# breakout.net
KiCad netlist of a schematic drawn in EAGLE
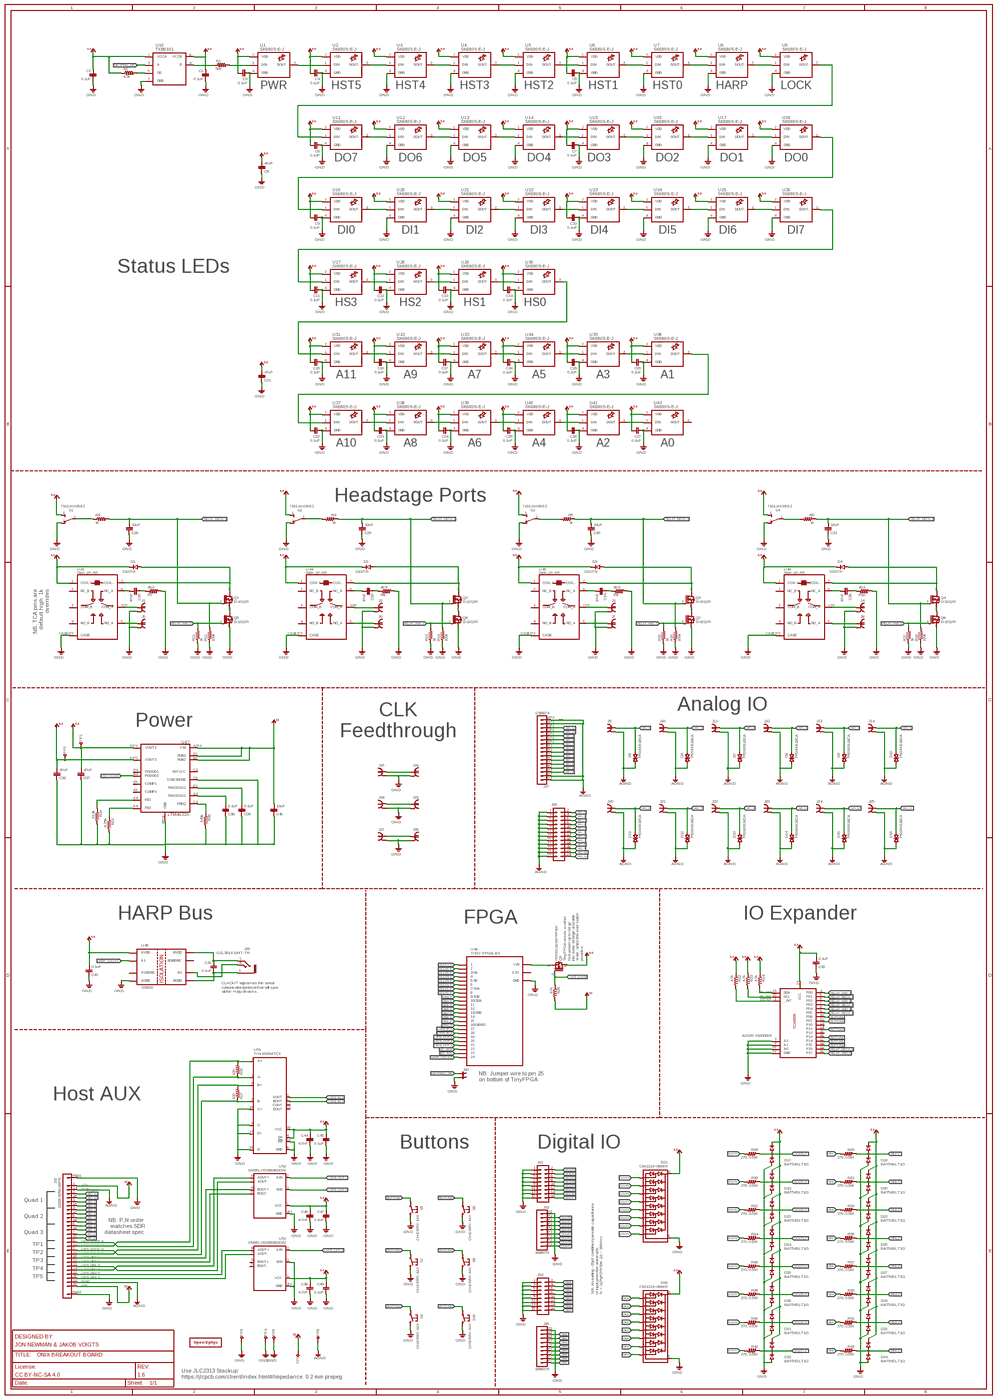
[diagram p0: schematic, sheet 1, overview]
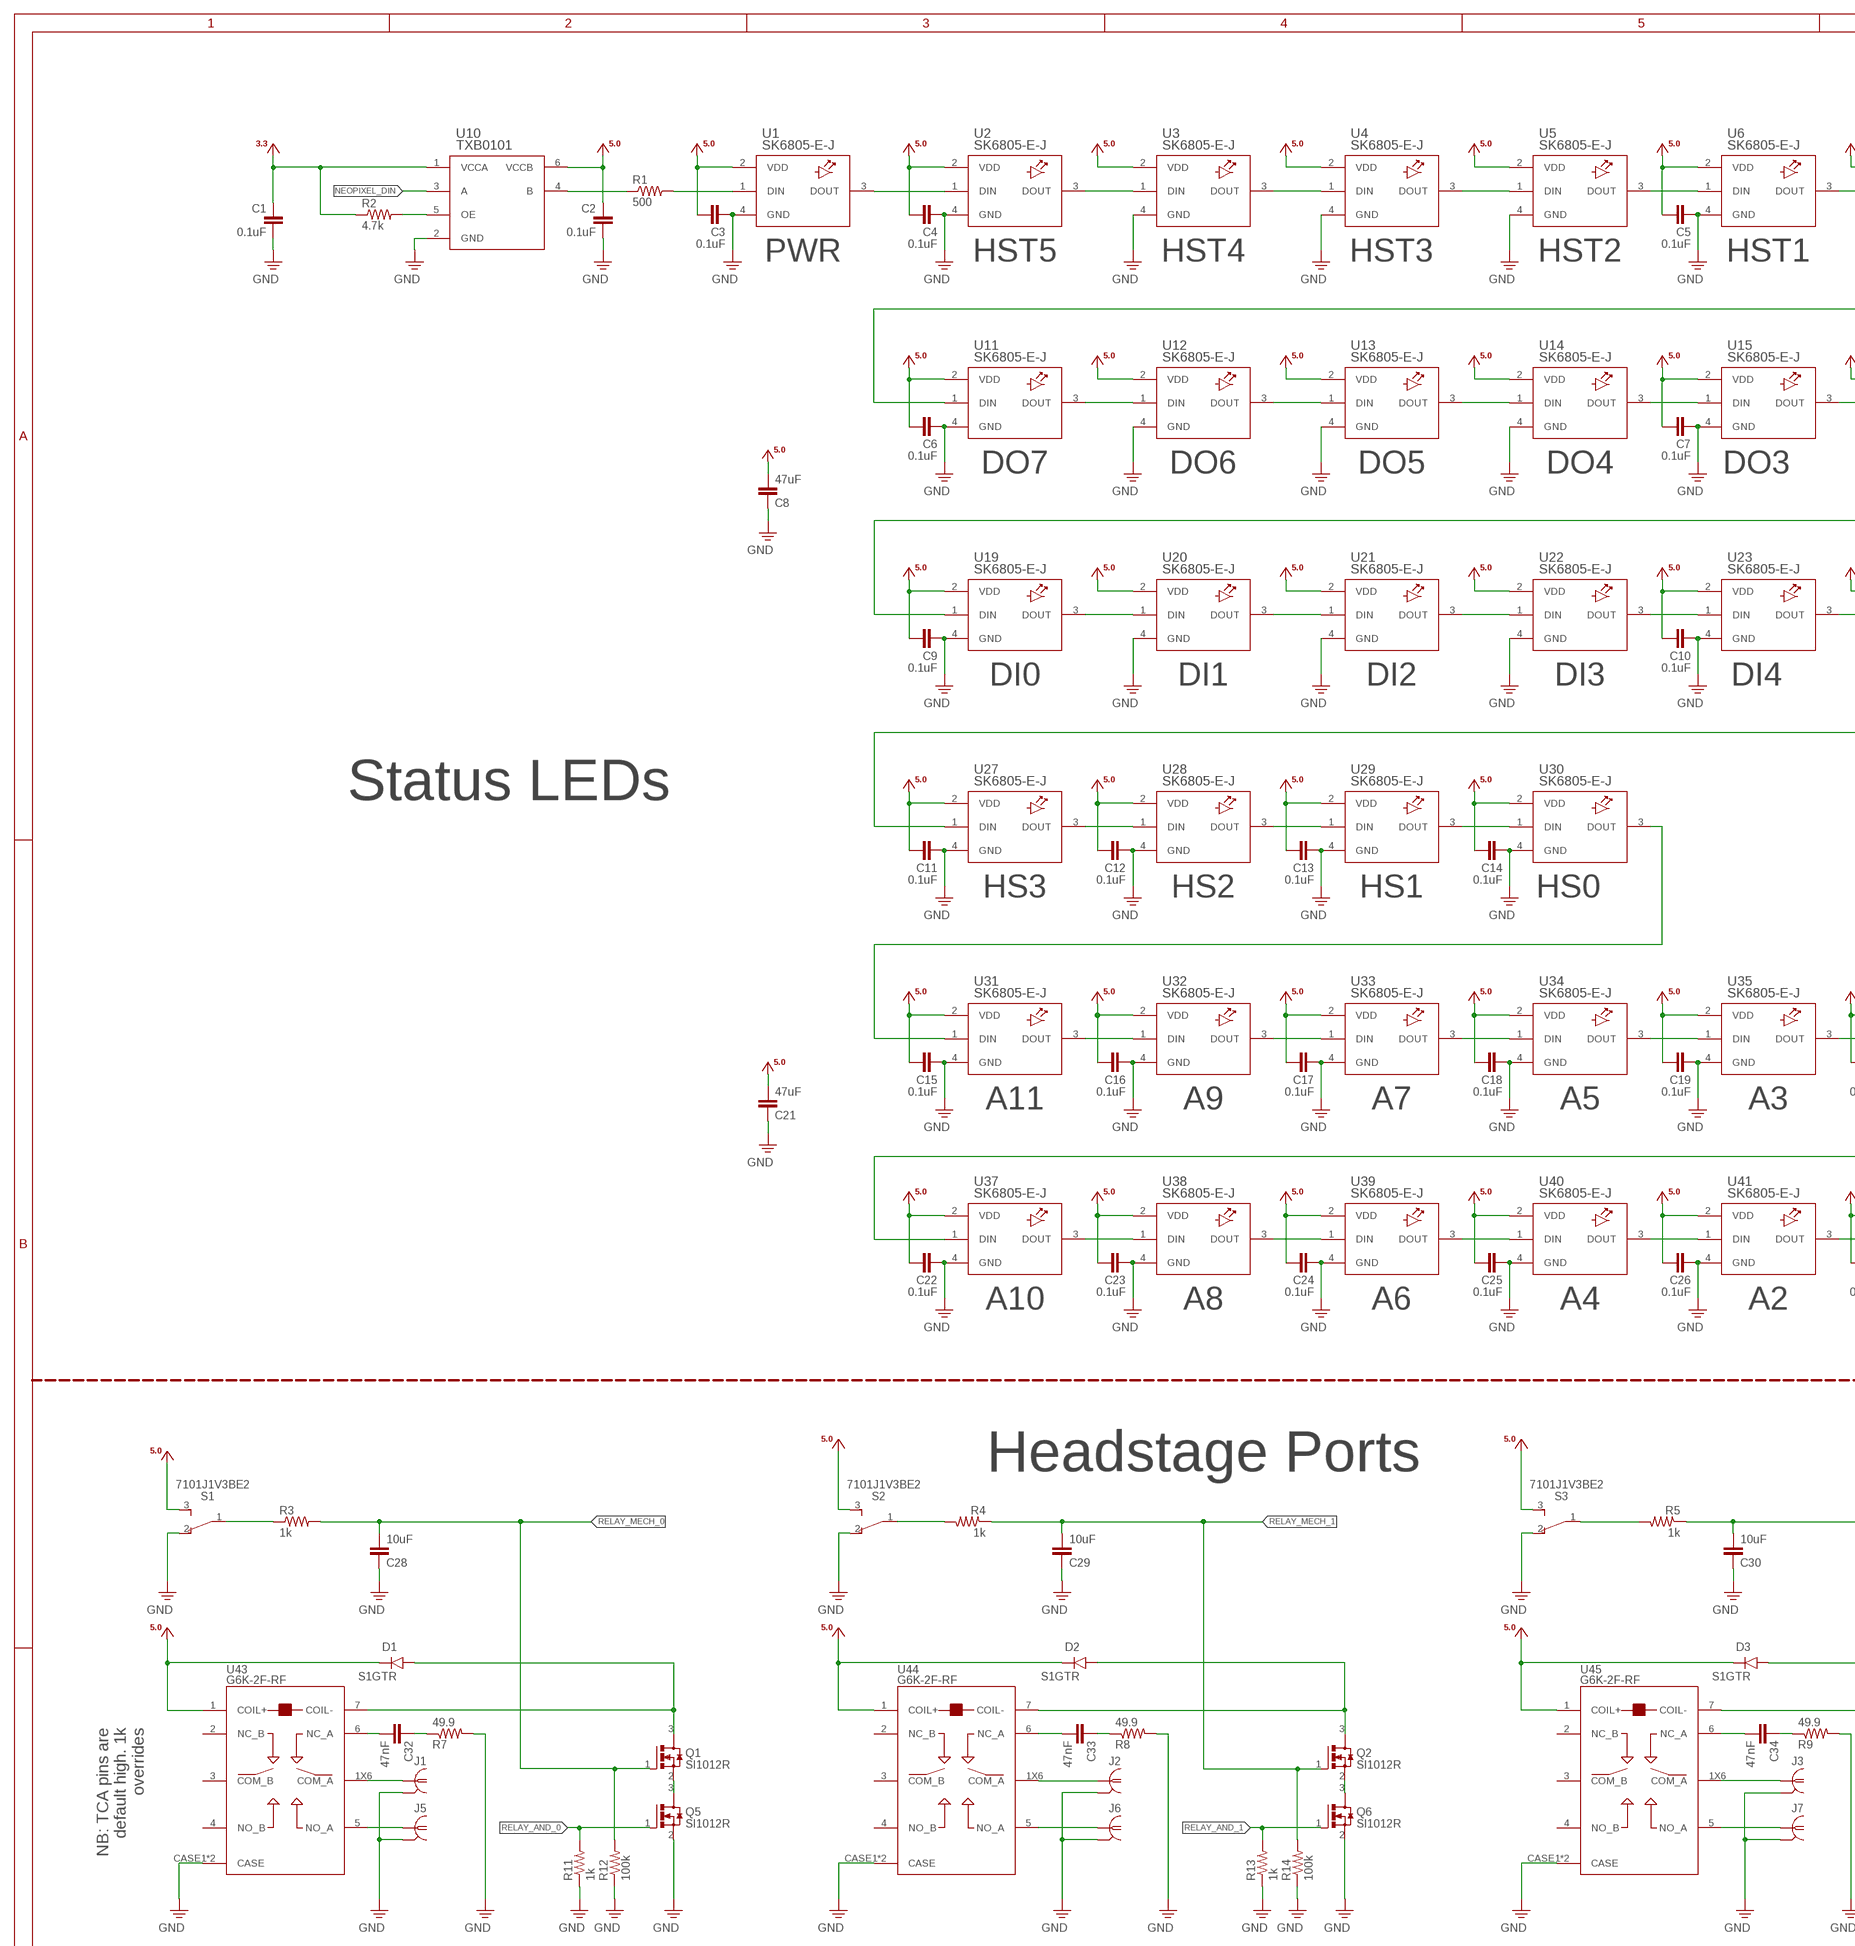
[diagram p1: schematic, sheet 1, part 1 of 4]
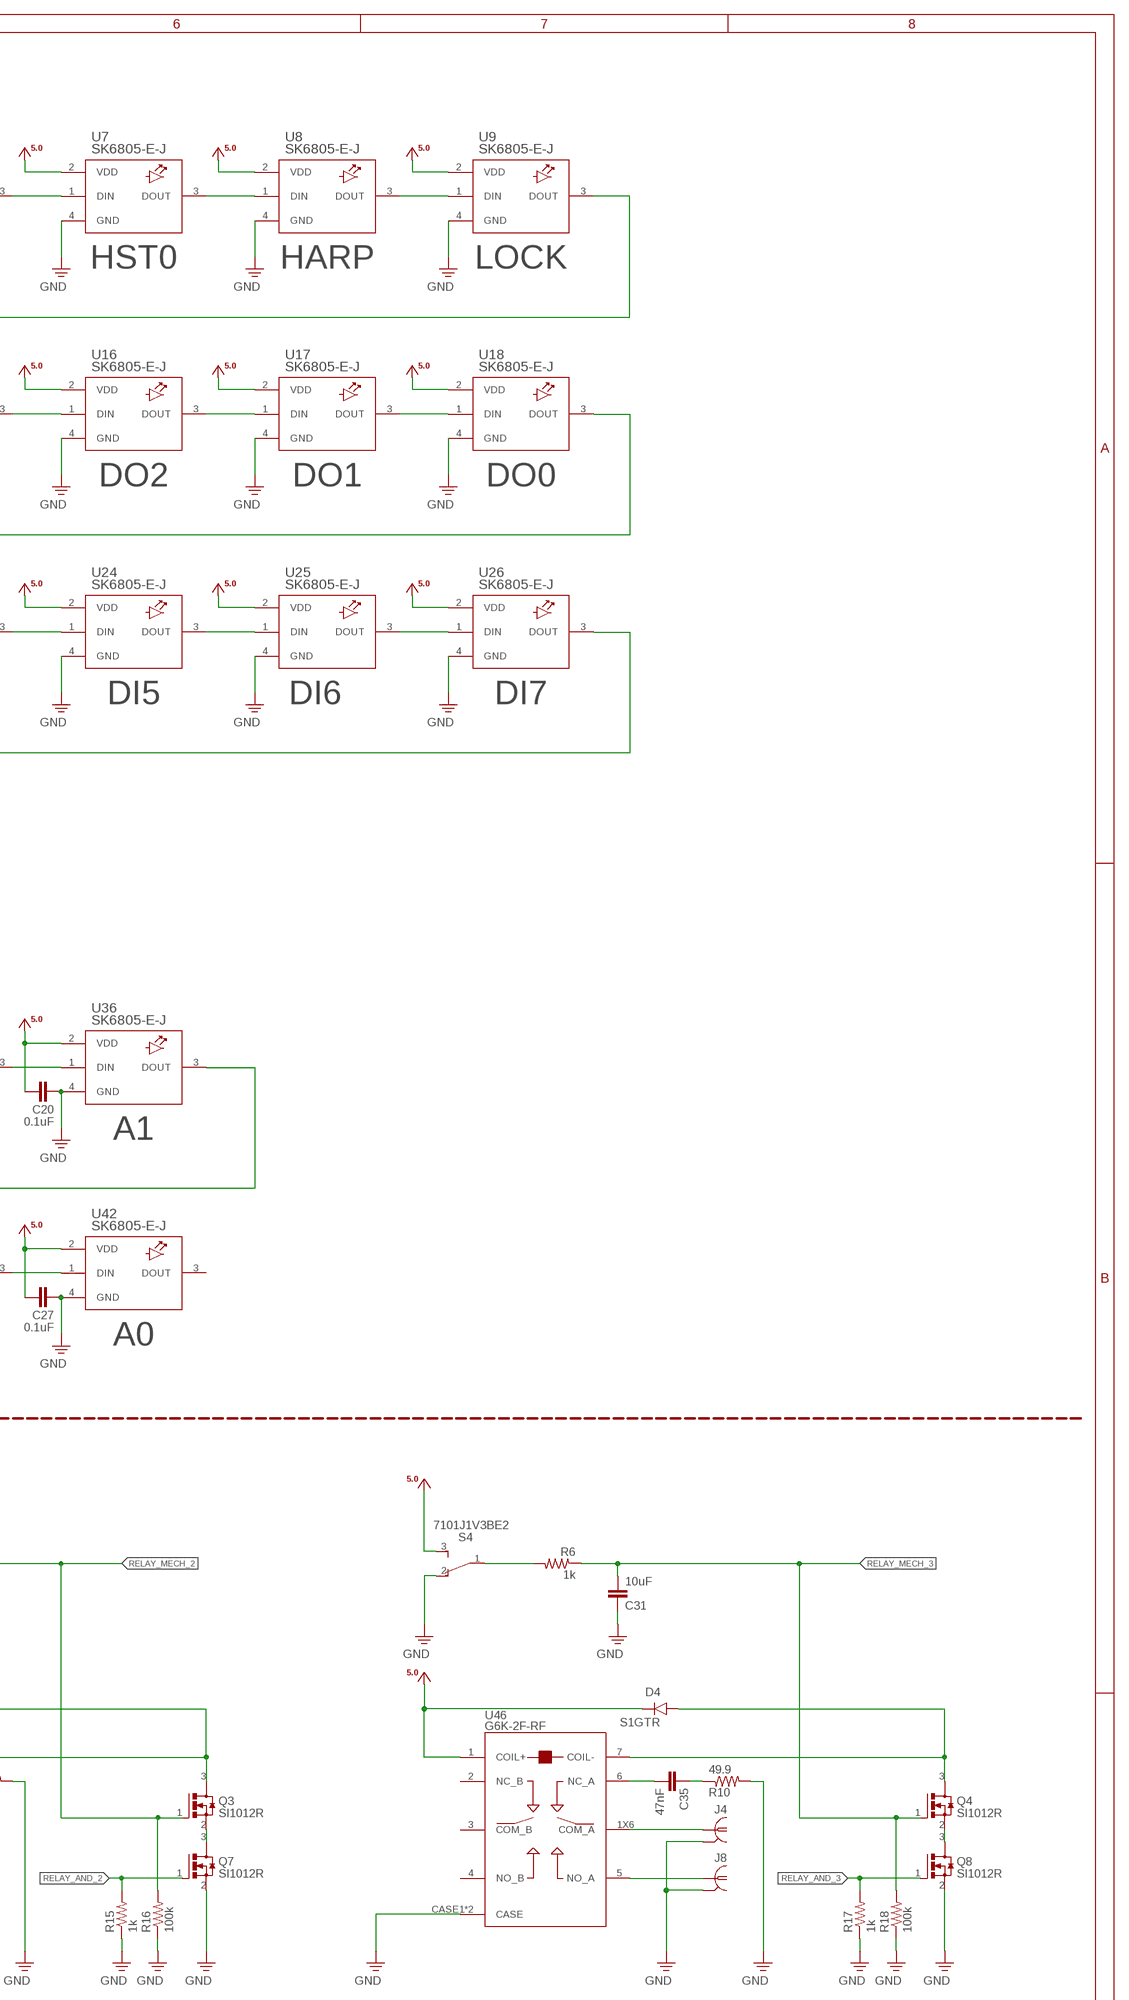
[diagram p2: schematic, sheet 1, part 2 of 4]
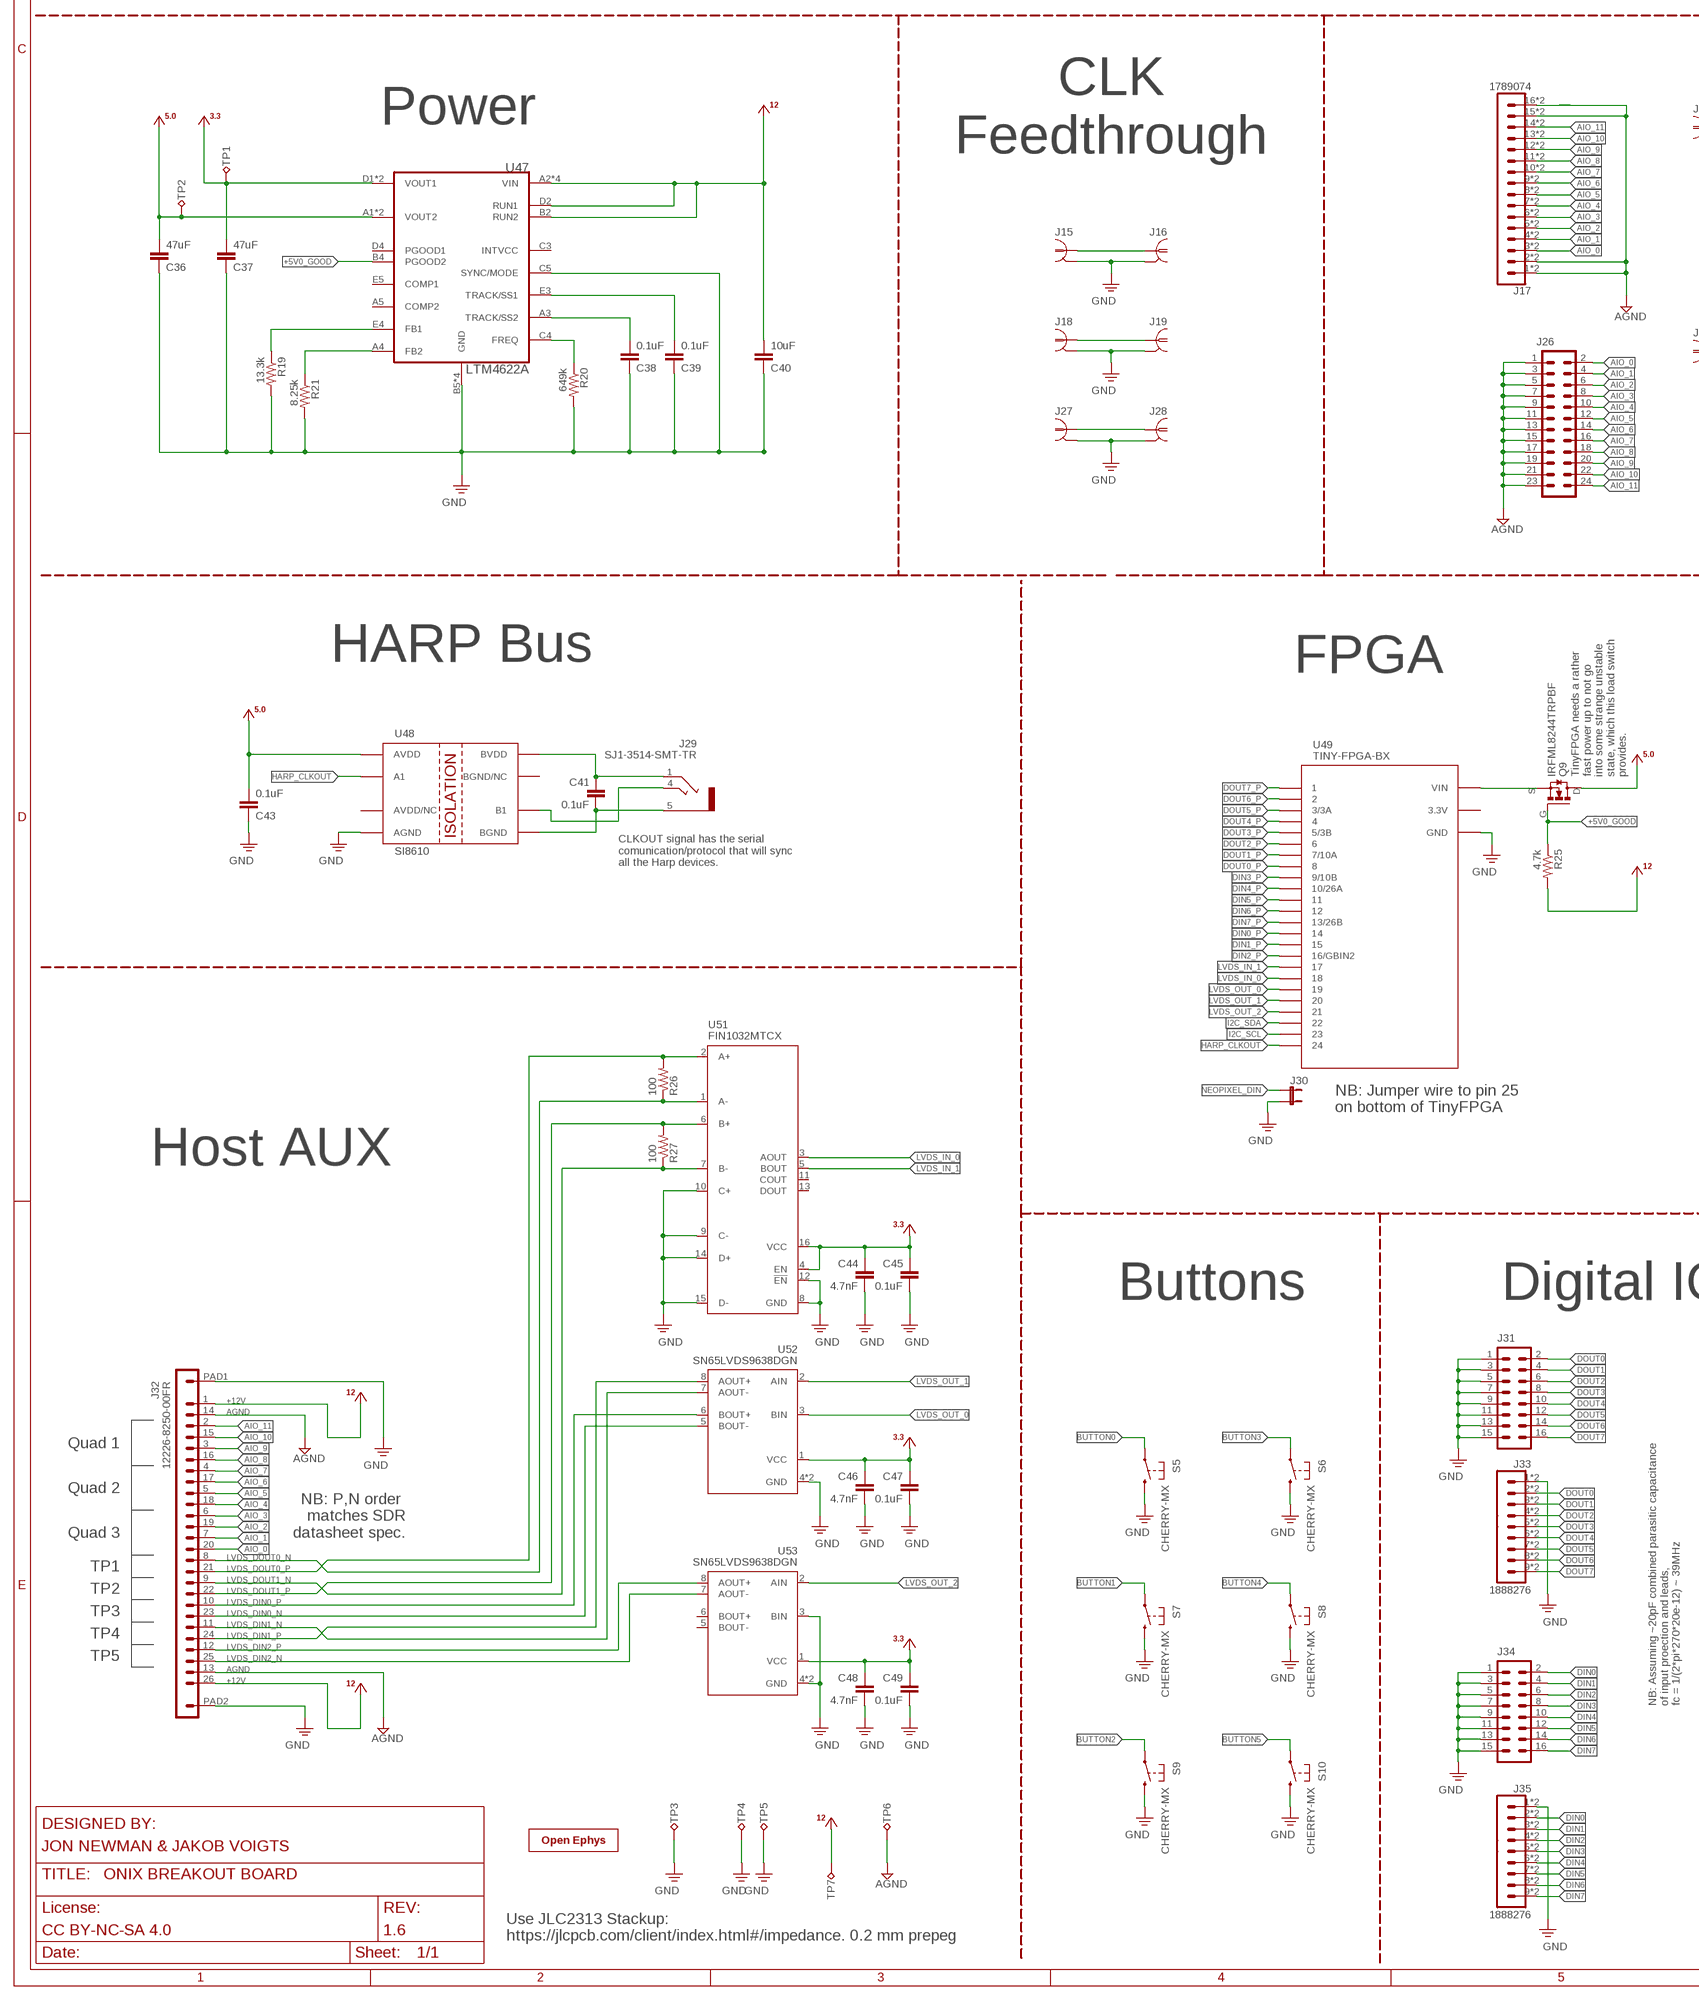
[diagram p3: schematic, sheet 1, part 3 of 4]
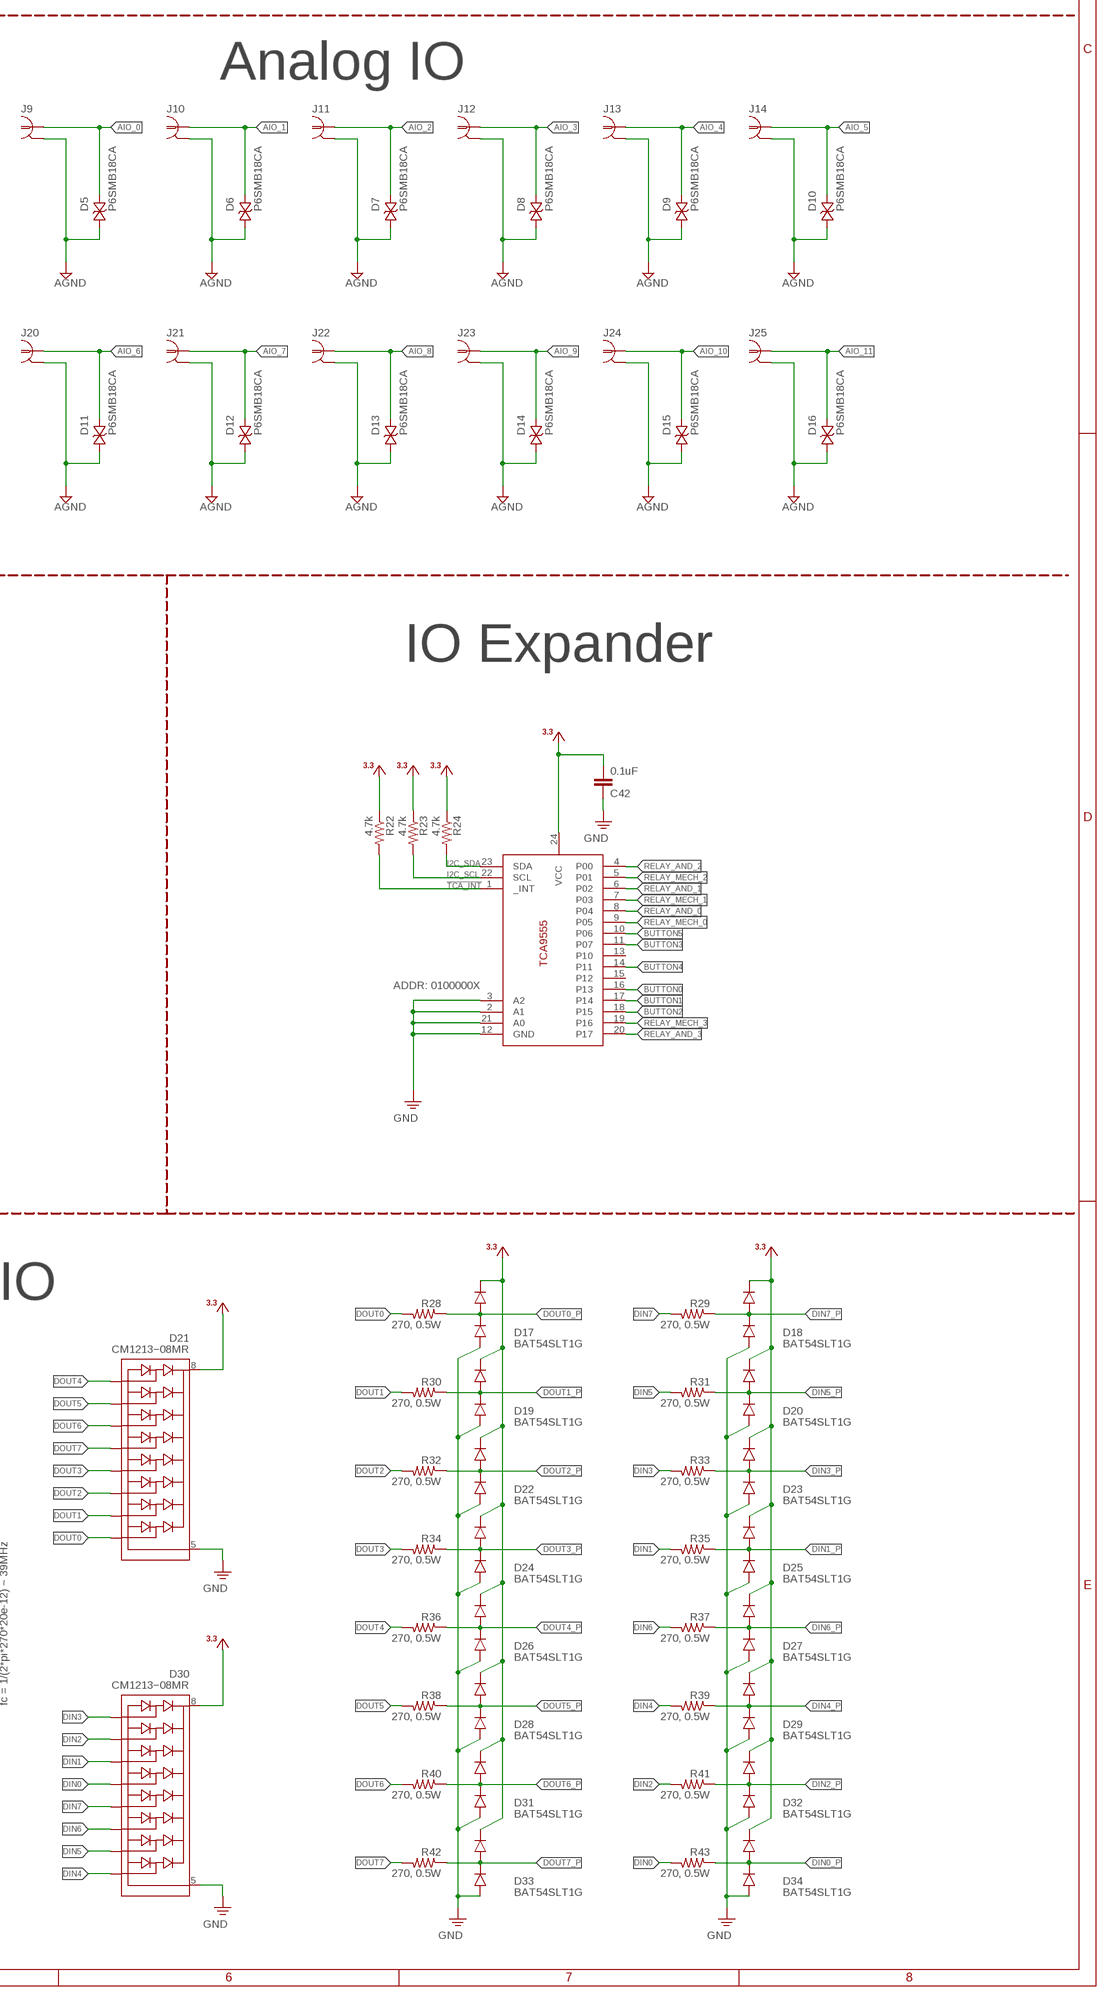
[diagram p4: schematic, sheet 1, part 4 of 4]

(export (version "E")
  (design (tool "Eeschema 10.0.6"))
  (components
    (comp (ref "C1")
      (value "0.1uF")
      (footprint "eagle-import:0402")
      (libsource (lib "eagle-import") (part "C_0402"))
    )
    (comp (ref "C2")
      (value "0.1uF")
      (footprint "eagle-import:0402")
      (libsource (lib "eagle-import") (part "C_0402"))
    )
    (comp (ref "C3")
      (value "0.1uF")
      (footprint "eagle-import:0402")
      (libsource (lib "eagle-import") (part "C_0402"))
    )
    (comp (ref "C4")
      (value "0.1uF")
      (footprint "eagle-import:0402")
      (libsource (lib "eagle-import") (part "C_0402"))
    )
    (comp (ref "C5")
      (value "0.1uF")
      (footprint "eagle-import:0402")
      (libsource (lib "eagle-import") (part "C_0402"))
    )
    (comp (ref "C6")
      (value "0.1uF")
      (footprint "eagle-import:0402")
      (libsource (lib "eagle-import") (part "C_0402"))
    )
    (comp (ref "C7")
      (value "0.1uF")
      (footprint "eagle-import:0402")
      (libsource (lib "eagle-import") (part "C_0402"))
    )
    (comp (ref "C8")
      (value "47uF")
      (footprint "eagle-import:1210")
      (libsource (lib "eagle-import") (part "C_1210"))
    )
    (comp (ref "C9")
      (value "0.1uF")
      (footprint "eagle-import:0402")
      (libsource (lib "eagle-import") (part "C_0402"))
    )
    (comp (ref "C10")
      (value "0.1uF")
      (footprint "eagle-import:0402")
      (libsource (lib "eagle-import") (part "C_0402"))
    )
    (comp (ref "C11")
      (value "0.1uF")
      (footprint "eagle-import:0402")
      (libsource (lib "eagle-import") (part "C_0402"))
    )
    (comp (ref "C12")
      (value "0.1uF")
      (footprint "eagle-import:0402")
      (libsource (lib "eagle-import") (part "C_0402"))
    )
    (comp (ref "C13")
      (value "0.1uF")
      (footprint "eagle-import:0402")
      (libsource (lib "eagle-import") (part "C_0402"))
    )
    (comp (ref "C14")
      (value "0.1uF")
      (footprint "eagle-import:0402")
      (libsource (lib "eagle-import") (part "C_0402"))
    )
    (comp (ref "C15")
      (value "0.1uF")
      (footprint "eagle-import:0402")
      (libsource (lib "eagle-import") (part "C_0402"))
    )
    (comp (ref "C16")
      (value "0.1uF")
      (footprint "eagle-import:0402")
      (libsource (lib "eagle-import") (part "C_0402"))
    )
    (comp (ref "C17")
      (value "0.1uF")
      (footprint "eagle-import:0402")
      (libsource (lib "eagle-import") (part "C_0402"))
    )
    (comp (ref "C18")
      (value "0.1uF")
      (footprint "eagle-import:0402")
      (libsource (lib "eagle-import") (part "C_0402"))
    )
    (comp (ref "C19")
      (value "0.1uF")
      (footprint "eagle-import:0402")
      (libsource (lib "eagle-import") (part "C_0402"))
    )
    (comp (ref "C20")
      (value "0.1uF")
      (footprint "eagle-import:0402")
      (libsource (lib "eagle-import") (part "C_0402"))
    )
    (comp (ref "C21")
      (value "47uF")
      (footprint "eagle-import:1210")
      (libsource (lib "eagle-import") (part "C_1210"))
    )
    (comp (ref "C22")
      (value "0.1uF")
      (footprint "eagle-import:0402")
      (libsource (lib "eagle-import") (part "C_0402"))
    )
    (comp (ref "C23")
      (value "0.1uF")
      (footprint "eagle-import:0402")
      (libsource (lib "eagle-import") (part "C_0402"))
    )
    (comp (ref "C24")
      (value "0.1uF")
      (footprint "eagle-import:0402")
      (libsource (lib "eagle-import") (part "C_0402"))
    )
    (comp (ref "C25")
      (value "0.1uF")
      (footprint "eagle-import:0402")
      (libsource (lib "eagle-import") (part "C_0402"))
    )
    (comp (ref "C26")
      (value "0.1uF")
      (footprint "eagle-import:0402")
      (libsource (lib "eagle-import") (part "C_0402"))
    )
    (comp (ref "C27")
      (value "0.1uF")
      (footprint "eagle-import:0402")
      (libsource (lib "eagle-import") (part "C_0402"))
    )
    (comp (ref "C28")
      (value "10uF")
      (footprint "eagle-import:0805")
      (fields (field (name "PARTNO") "C2012X5R1Cxxxxxxx"))
      (libsource (lib "eagle-import") (part "C_0805"))
    )
    (comp (ref "C29")
      (value "10uF")
      (footprint "eagle-import:0805")
      (fields (field (name "PARTNO") "C2012X5R1Cxxxxxxx"))
      (libsource (lib "eagle-import") (part "C_0805"))
    )
    (comp (ref "C30")
      (value "10uF")
      (footprint "eagle-import:0805")
      (fields (field (name "PARTNO") "C2012X5R1Cxxxxxxx"))
      (libsource (lib "eagle-import") (part "C_0805"))
    )
    (comp (ref "C31")
      (value "10uF")
      (footprint "eagle-import:0805")
      (fields (field (name "PARTNO") "C2012X5R1Cxxxxxxx"))
      (libsource (lib "eagle-import") (part "C_0805"))
    )
    (comp (ref "C32")
      (value "47nF")
      (footprint "eagle-import:0402")
      (libsource (lib "eagle-import") (part "C_0402"))
    )
    (comp (ref "C33")
      (value "47nF")
      (footprint "eagle-import:0402")
      (libsource (lib "eagle-import") (part "C_0402"))
    )
    (comp (ref "C34")
      (value "47nF")
      (footprint "eagle-import:0402")
      (libsource (lib "eagle-import") (part "C_0402"))
    )
    (comp (ref "C35")
      (value "47nF")
      (footprint "eagle-import:0402")
      (libsource (lib "eagle-import") (part "C_0402"))
    )
    (comp (ref "C36")
      (value "47uF")
      (footprint "eagle-import:1210")
      (libsource (lib "eagle-import") (part "C_1210"))
    )
    (comp (ref "C37")
      (value "47uF")
      (footprint "eagle-import:1210")
      (libsource (lib "eagle-import") (part "C_1210"))
    )
    (comp (ref "C38")
      (value "0.1uF")
      (footprint "eagle-import:0402")
      (libsource (lib "eagle-import") (part "C_0402"))
    )
    (comp (ref "C39")
      (value "0.1uF")
      (footprint "eagle-import:0402")
      (libsource (lib "eagle-import") (part "C_0402"))
    )
    (comp (ref "C40")
      (value "10uF")
      (footprint "eagle-import:0805")
      (fields (field (name "PARTNO") "C2012X5R1Cxxxxxxx"))
      (libsource (lib "eagle-import") (part "C_0805"))
    )
    (comp (ref "C41")
      (value "0.1uF")
      (footprint "eagle-import:0402")
      (libsource (lib "eagle-import") (part "C_0402"))
    )
    (comp (ref "C42")
      (value "0.1uF")
      (footprint "eagle-import:0402")
      (libsource (lib "eagle-import") (part "C_0402"))
    )
    (comp (ref "C43")
      (value "0.1uF")
      (footprint "eagle-import:0402")
      (libsource (lib "eagle-import") (part "C_0402"))
    )
    (comp (ref "C44")
      (value "4.7nF")
      (footprint "eagle-import:0402")
      (libsource (lib "eagle-import") (part "C_0402"))
    )
    (comp (ref "C45")
      (value "0.1uF")
      (footprint "eagle-import:0402")
      (libsource (lib "eagle-import") (part "C_0402"))
    )
    (comp (ref "C46")
      (value "4.7nF")
      (footprint "eagle-import:0402")
      (libsource (lib "eagle-import") (part "C_0402"))
    )
    (comp (ref "C47")
      (value "0.1uF")
      (footprint "eagle-import:0402")
      (libsource (lib "eagle-import") (part "C_0402"))
    )
    (comp (ref "C48")
      (value "4.7nF")
      (footprint "eagle-import:0402")
      (libsource (lib "eagle-import") (part "C_0402"))
    )
    (comp (ref "C49")
      (value "0.1uF")
      (footprint "eagle-import:0402")
      (libsource (lib "eagle-import") (part "C_0402"))
    )
    (comp (ref "D1")
      (value "S1GTR")
      (footprint "eagle-import:SMA-DO214AC")
      (libsource (lib "eagle-import") (part "DIODE_S1B-13-F"))
    )
    (comp (ref "D2")
      (value "S1GTR")
      (footprint "eagle-import:SMA-DO214AC")
      (libsource (lib "eagle-import") (part "DIODE_S1B-13-F"))
    )
    (comp (ref "D3")
      (value "S1GTR")
      (footprint "eagle-import:SMA-DO214AC")
      (libsource (lib "eagle-import") (part "DIODE_S1B-13-F"))
    )
    (comp (ref "D4")
      (value "S1GTR")
      (footprint "eagle-import:SMA-DO214AC")
      (libsource (lib "eagle-import") (part "DIODE_S1B-13-F"))
    )
    (comp (ref "D5")
      (value "P6SMB18CA")
      (footprint "eagle-import:SMA-DO214AC")
      (libsource (lib "eagle-import") (part "TVS-DIODE-BI_DO214"))
    )
    (comp (ref "D6")
      (value "P6SMB18CA")
      (footprint "eagle-import:SMA-DO214AC")
      (libsource (lib "eagle-import") (part "TVS-DIODE-BI_DO214"))
    )
    (comp (ref "D7")
      (value "P6SMB18CA")
      (footprint "eagle-import:SMA-DO214AC")
      (libsource (lib "eagle-import") (part "TVS-DIODE-BI_DO214"))
    )
    (comp (ref "D8")
      (value "P6SMB18CA")
      (footprint "eagle-import:SMA-DO214AC")
      (libsource (lib "eagle-import") (part "TVS-DIODE-BI_DO214"))
    )
    (comp (ref "D9")
      (value "P6SMB18CA")
      (footprint "eagle-import:SMA-DO214AC")
      (libsource (lib "eagle-import") (part "TVS-DIODE-BI_DO214"))
    )
    (comp (ref "D10")
      (value "P6SMB18CA")
      (footprint "eagle-import:SMA-DO214AC")
      (libsource (lib "eagle-import") (part "TVS-DIODE-BI_DO214"))
    )
    (comp (ref "D11")
      (value "P6SMB18CA")
      (footprint "eagle-import:SMA-DO214AC")
      (libsource (lib "eagle-import") (part "TVS-DIODE-BI_DO214"))
    )
    (comp (ref "D12")
      (value "P6SMB18CA")
      (footprint "eagle-import:SMA-DO214AC")
      (libsource (lib "eagle-import") (part "TVS-DIODE-BI_DO214"))
    )
    (comp (ref "D13")
      (value "P6SMB18CA")
      (footprint "eagle-import:SMA-DO214AC")
      (libsource (lib "eagle-import") (part "TVS-DIODE-BI_DO214"))
    )
    (comp (ref "D14")
      (value "P6SMB18CA")
      (footprint "eagle-import:SMA-DO214AC")
      (libsource (lib "eagle-import") (part "TVS-DIODE-BI_DO214"))
    )
    (comp (ref "D15")
      (value "P6SMB18CA")
      (footprint "eagle-import:SMA-DO214AC")
      (libsource (lib "eagle-import") (part "TVS-DIODE-BI_DO214"))
    )
    (comp (ref "D16")
      (value "P6SMB18CA")
      (footprint "eagle-import:SMA-DO214AC")
      (libsource (lib "eagle-import") (part "TVS-DIODE-BI_DO214"))
    )
    (comp (ref "D17")
      (value "BAT54SLT1G")
      (footprint "eagle-import:SOT23")
      (libsource (lib "eagle-import") (part "DIODE2_SOT23"))
    )
    (comp (ref "D18")
      (value "BAT54SLT1G")
      (footprint "eagle-import:SOT23")
      (libsource (lib "eagle-import") (part "DIODE2_SOT23"))
    )
    (comp (ref "D19")
      (value "BAT54SLT1G")
      (footprint "eagle-import:SOT23")
      (libsource (lib "eagle-import") (part "DIODE2_SOT23"))
    )
    (comp (ref "D20")
      (value "BAT54SLT1G")
      (footprint "eagle-import:SOT23")
      (libsource (lib "eagle-import") (part "DIODE2_SOT23"))
    )
    (comp (ref "D21")
      (value "CM1213−08MR")
      (footprint "eagle-import:MSOP-10-3X3")
      (libsource (lib "eagle-import") (part "TVS-DIODE-BI-8_MSOP"))
    )
    (comp (ref "D22")
      (value "BAT54SLT1G")
      (footprint "eagle-import:SOT23")
      (libsource (lib "eagle-import") (part "DIODE2_SOT23"))
    )
    (comp (ref "D23")
      (value "BAT54SLT1G")
      (footprint "eagle-import:SOT23")
      (libsource (lib "eagle-import") (part "DIODE2_SOT23"))
    )
    (comp (ref "D24")
      (value "BAT54SLT1G")
      (footprint "eagle-import:SOT23")
      (libsource (lib "eagle-import") (part "DIODE2_SOT23"))
    )
    (comp (ref "D25")
      (value "BAT54SLT1G")
      (footprint "eagle-import:SOT23")
      (libsource (lib "eagle-import") (part "DIODE2_SOT23"))
    )
    (comp (ref "D26")
      (value "BAT54SLT1G")
      (footprint "eagle-import:SOT23")
      (libsource (lib "eagle-import") (part "DIODE2_SOT23"))
    )
    (comp (ref "D27")
      (value "BAT54SLT1G")
      (footprint "eagle-import:SOT23")
      (libsource (lib "eagle-import") (part "DIODE2_SOT23"))
    )
    (comp (ref "D28")
      (value "BAT54SLT1G")
      (footprint "eagle-import:SOT23")
      (libsource (lib "eagle-import") (part "DIODE2_SOT23"))
    )
    (comp (ref "D29")
      (value "BAT54SLT1G")
      (footprint "eagle-import:SOT23")
      (libsource (lib "eagle-import") (part "DIODE2_SOT23"))
    )
    (comp (ref "D30")
      (value "CM1213−08MR")
      (footprint "eagle-import:MSOP-10-3X3")
      (libsource (lib "eagle-import") (part "TVS-DIODE-BI-8_MSOP"))
    )
    (comp (ref "D31")
      (value "BAT54SLT1G")
      (footprint "eagle-import:SOT23")
      (libsource (lib "eagle-import") (part "DIODE2_SOT23"))
    )
    (comp (ref "D32")
      (value "BAT54SLT1G")
      (footprint "eagle-import:SOT23")
      (libsource (lib "eagle-import") (part "DIODE2_SOT23"))
    )
    (comp (ref "D33")
      (value "BAT54SLT1G")
      (footprint "eagle-import:SOT23")
      (libsource (lib "eagle-import") (part "DIODE2_SOT23"))
    )
    (comp (ref "D34")
      (value "BAT54SLT1G")
      (footprint "eagle-import:SOT23")
      (libsource (lib "eagle-import") (part "DIODE2_SOT23"))
    )
    (comp (ref "J1")
      (value "COAX_SMA-VERT")
      (footprint "eagle-import:SMA_JACK_142-0701-201")
      (libsource (lib "eagle-import") (part "COAX_SMA-VERT"))
    )
    (comp (ref "J2")
      (value "COAX_SMA-VERT")
      (footprint "eagle-import:SMA_JACK_142-0701-201")
      (libsource (lib "eagle-import") (part "COAX_SMA-VERT"))
    )
    (comp (ref "J3")
      (value "COAX_SMA-VERT")
      (footprint "eagle-import:SMA_JACK_142-0701-201")
      (libsource (lib "eagle-import") (part "COAX_SMA-VERT"))
    )
    (comp (ref "J4")
      (value "COAX_SMA-VERT")
      (footprint "eagle-import:SMA_JACK_142-0701-201")
      (libsource (lib "eagle-import") (part "COAX_SMA-VERT"))
    )
    (comp (ref "J5")
      (value "COAX_MMCX-THRU")
      (footprint "eagle-import:MMCX-THRU")
      (libsource (lib "eagle-import") (part "COAX_MMCX-THRU"))
    )
    (comp (ref "J6")
      (value "COAX_MMCX-THRU")
      (footprint "eagle-import:MMCX-THRU")
      (libsource (lib "eagle-import") (part "COAX_MMCX-THRU"))
    )
    (comp (ref "J7")
      (value "COAX_MMCX-THRU")
      (footprint "eagle-import:MMCX-THRU")
      (libsource (lib "eagle-import") (part "COAX_MMCX-THRU"))
    )
    (comp (ref "J8")
      (value "COAX_MMCX-THRU")
      (footprint "eagle-import:MMCX-THRU")
      (libsource (lib "eagle-import") (part "COAX_MMCX-THRU"))
    )
    (comp (ref "J9")
      (value "COAX_0731010360")
      (footprint "eagle-import:0731010360")
      (libsource (lib "eagle-import") (part "COAX_0731010360"))
    )
    (comp (ref "J10")
      (value "COAX_0731010360")
      (footprint "eagle-import:0731010360")
      (libsource (lib "eagle-import") (part "COAX_0731010360"))
    )
    (comp (ref "J11")
      (value "COAX_0731010360")
      (footprint "eagle-import:0731010360")
      (libsource (lib "eagle-import") (part "COAX_0731010360"))
    )
    (comp (ref "J12")
      (value "COAX_0731010360")
      (footprint "eagle-import:0731010360")
      (libsource (lib "eagle-import") (part "COAX_0731010360"))
    )
    (comp (ref "J13")
      (value "COAX_0731010360")
      (footprint "eagle-import:0731010360")
      (libsource (lib "eagle-import") (part "COAX_0731010360"))
    )
    (comp (ref "J14")
      (value "COAX_0731010360")
      (footprint "eagle-import:0731010360")
      (libsource (lib "eagle-import") (part "COAX_0731010360"))
    )
    (comp (ref "J15")
      (value "COAX_MMCX-THRU")
      (footprint "eagle-import:MMCX-THRU")
      (libsource (lib "eagle-import") (part "COAX_MMCX-THRU"))
    )
    (comp (ref "J16")
      (value "COAX_SMA-VERT")
      (footprint "eagle-import:SMA_JACK_142-0701-201")
      (libsource (lib "eagle-import") (part "COAX_SMA-VERT"))
    )
    (comp (ref "J17")
      (value "1789074")
      (footprint "eagle-import:SCREW16-2")
      (libsource (lib "eagle-import") (part "PINHD-1X16"))
    )
    (comp (ref "J18")
      (value "COAX_MMCX-THRU")
      (footprint "eagle-import:MMCX-THRU")
      (libsource (lib "eagle-import") (part "COAX_MMCX-THRU"))
    )
    (comp (ref "J19")
      (value "COAX_SMA-VERT")
      (footprint "eagle-import:SMA_JACK_142-0701-201")
      (libsource (lib "eagle-import") (part "COAX_SMA-VERT"))
    )
    (comp (ref "J20")
      (value "COAX_0731010360")
      (footprint "eagle-import:0731010360")
      (libsource (lib "eagle-import") (part "COAX_0731010360"))
    )
    (comp (ref "J21")
      (value "COAX_0731010360")
      (footprint "eagle-import:0731010360")
      (libsource (lib "eagle-import") (part "COAX_0731010360"))
    )
    (comp (ref "J22")
      (value "COAX_0731010360")
      (footprint "eagle-import:0731010360")
      (libsource (lib "eagle-import") (part "COAX_0731010360"))
    )
    (comp (ref "J23")
      (value "COAX_0731010360")
      (footprint "eagle-import:0731010360")
      (libsource (lib "eagle-import") (part "COAX_0731010360"))
    )
    (comp (ref "J24")
      (value "COAX_0731010360")
      (footprint "eagle-import:0731010360")
      (libsource (lib "eagle-import") (part "COAX_0731010360"))
    )
    (comp (ref "J25")
      (value "COAX_0731010360")
      (footprint "eagle-import:0731010360")
      (libsource (lib "eagle-import") (part "COAX_0731010360"))
    )
    (comp (ref "J26")
      (value "69168-124HLF")
      (footprint "eagle-import:2X12-BIG")
      (libsource (lib "eagle-import") (part "PINHD-2X12_0.1{dblquote}"))
    )
    (comp (ref "J27")
      (value "COAX_MMCX-THRU")
      (footprint "eagle-import:MMCX-THRU")
      (libsource (lib "eagle-import") (part "COAX_MMCX-THRU"))
    )
    (comp (ref "J28")
      (value "COAX_SMA-VERT")
      (footprint "eagle-import:SMA_JACK_142-0701-201")
      (libsource (lib "eagle-import") (part "COAX_SMA-VERT"))
    )
    (comp (ref "J29")
      (value "SJ1-3514-SMT-TR")
      (footprint "eagle-import:35RASMT2BHNTRX")
      (libsource (lib "eagle-import") (part "STEREO_JACK"))
    )
    (comp (ref "J30")
      (value "JP2E_THRU-HOLE")
      (footprint "eagle-import:JP2")
      (libsource (lib "eagle-import") (part "JP2E_THRU-HOLE"))
    )
    (comp (ref "J31")
      (value "69168-116HLF")
      (footprint "eagle-import:2X08-BIG")
      (libsource (lib "eagle-import") (part "PINHD-2X8_THRU"))
    )
    (comp (ref "J32")
      (value "12226-8250-00FR")
      (footprint "eagle-import:12226-82X0-00XX")
      (libsource (lib "eagle-import") (part "PINHD-1X26_122"))
    )
    (comp (ref "J33")
      (value "1888276")
      (footprint "eagle-import:SCREW9-2")
      (libsource (lib "eagle-import") (part "PINHD-1X9_SCREW2"))
    )
    (comp (ref "J34")
      (value "69168-116HLF")
      (footprint "eagle-import:2X08-BIG")
      (libsource (lib "eagle-import") (part "PINHD-2X8_THRU"))
    )
    (comp (ref "J35")
      (value "1888276")
      (footprint "eagle-import:SCREW9-2")
      (libsource (lib "eagle-import") (part "PINHD-1X9_SCREW2"))
    )
    (comp (ref "Q1")
      (value "SI1012R")
      (footprint "eagle-import:SC75")
      (libsource (lib "eagle-import") (part "N-MOSFET_SC75-GSD"))
    )
    (comp (ref "Q2")
      (value "SI1012R")
      (footprint "eagle-import:SC75")
      (libsource (lib "eagle-import") (part "N-MOSFET_SC75-GSD"))
    )
    (comp (ref "Q3")
      (value "SI1012R")
      (footprint "eagle-import:SC75")
      (libsource (lib "eagle-import") (part "N-MOSFET_SC75-GSD"))
    )
    (comp (ref "Q4")
      (value "SI1012R")
      (footprint "eagle-import:SC75")
      (libsource (lib "eagle-import") (part "N-MOSFET_SC75-GSD"))
    )
    (comp (ref "Q5")
      (value "SI1012R")
      (footprint "eagle-import:SC75")
      (libsource (lib "eagle-import") (part "N-MOSFET_SC75-GSD"))
    )
    (comp (ref "Q6")
      (value "SI1012R")
      (footprint "eagle-import:SC75")
      (libsource (lib "eagle-import") (part "N-MOSFET_SC75-GSD"))
    )
    (comp (ref "Q7")
      (value "SI1012R")
      (footprint "eagle-import:SC75")
      (libsource (lib "eagle-import") (part "N-MOSFET_SC75-GSD"))
    )
    (comp (ref "Q8")
      (value "SI1012R")
      (footprint "eagle-import:SC75")
      (libsource (lib "eagle-import") (part "N-MOSFET_SC75-GSD"))
    )
    (comp (ref "Q9")
      (value "IRFML8244TRPBF")
      (footprint "eagle-import:SOT23-GSD")
      (libsource (lib "eagle-import") (part "N-MOSFET_SOT23-GSD"))
    )
    (comp (ref "R1")
      (value "500")
      (footprint "eagle-import:0402")
      (libsource (lib "eagle-import") (part "R_0402"))
    )
    (comp (ref "R2")
      (value "4.7k")
      (footprint "eagle-import:0402")
      (libsource (lib "eagle-import") (part "R_0402"))
    )
    (comp (ref "R3")
      (value "1k")
      (footprint "eagle-import:0402")
      (libsource (lib "eagle-import") (part "R_0402"))
    )
    (comp (ref "R4")
      (value "1k")
      (footprint "eagle-import:0402")
      (libsource (lib "eagle-import") (part "R_0402"))
    )
    (comp (ref "R5")
      (value "1k")
      (footprint "eagle-import:0402")
      (libsource (lib "eagle-import") (part "R_0402"))
    )
    (comp (ref "R6")
      (value "1k")
      (footprint "eagle-import:0402")
      (libsource (lib "eagle-import") (part "R_0402"))
    )
    (comp (ref "R7")
      (value "49.9")
      (footprint "eagle-import:0402")
      (libsource (lib "eagle-import") (part "R_0402"))
    )
    (comp (ref "R8")
      (value "49.9")
      (footprint "eagle-import:0402")
      (libsource (lib "eagle-import") (part "R_0402"))
    )
    (comp (ref "R9")
      (value "49.9")
      (footprint "eagle-import:0402")
      (libsource (lib "eagle-import") (part "R_0402"))
    )
    (comp (ref "R10")
      (value "49.9")
      (footprint "eagle-import:0402")
      (libsource (lib "eagle-import") (part "R_0402"))
    )
    (comp (ref "R11")
      (value "1k")
      (footprint "eagle-import:0402")
      (libsource (lib "eagle-import") (part "R_0402"))
    )
    (comp (ref "R12")
      (value "100k")
      (footprint "eagle-import:0402")
      (libsource (lib "eagle-import") (part "R_0402"))
    )
    (comp (ref "R13")
      (value "1k")
      (footprint "eagle-import:0402")
      (libsource (lib "eagle-import") (part "R_0402"))
    )
    (comp (ref "R14")
      (value "100k")
      (footprint "eagle-import:0402")
      (libsource (lib "eagle-import") (part "R_0402"))
    )
    (comp (ref "R15")
      (value "1k")
      (footprint "eagle-import:0402")
      (libsource (lib "eagle-import") (part "R_0402"))
    )
    (comp (ref "R16")
      (value "100k")
      (footprint "eagle-import:0402")
      (libsource (lib "eagle-import") (part "R_0402"))
    )
    (comp (ref "R17")
      (value "1k")
      (footprint "eagle-import:0402")
      (libsource (lib "eagle-import") (part "R_0402"))
    )
    (comp (ref "R18")
      (value "100k")
      (footprint "eagle-import:0402")
      (libsource (lib "eagle-import") (part "R_0402"))
    )
    (comp (ref "R19")
      (value "13.3k")
      (footprint "eagle-import:0402")
      (libsource (lib "eagle-import") (part "R_0402"))
    )
    (comp (ref "R20")
      (value "649k")
      (footprint "eagle-import:0402")
      (libsource (lib "eagle-import") (part "R_0402"))
    )
    (comp (ref "R21")
      (value "8.25k")
      (footprint "eagle-import:0402")
      (libsource (lib "eagle-import") (part "R_0402"))
    )
    (comp (ref "R22")
      (value "4.7k")
      (footprint "eagle-import:0402")
      (libsource (lib "eagle-import") (part "R_0402"))
    )
    (comp (ref "R23")
      (value "4.7k")
      (footprint "eagle-import:0402")
      (libsource (lib "eagle-import") (part "R_0402"))
    )
    (comp (ref "R24")
      (value "4.7k")
      (footprint "eagle-import:0402")
      (libsource (lib "eagle-import") (part "R_0402"))
    )
    (comp (ref "R25")
      (value "4.7k")
      (footprint "eagle-import:0402")
      (libsource (lib "eagle-import") (part "R_0402"))
    )
    (comp (ref "R26")
      (value "100")
      (footprint "eagle-import:0402")
      (libsource (lib "eagle-import") (part "R_0402"))
    )
    (comp (ref "R27")
      (value "100")
      (footprint "eagle-import:0402")
      (libsource (lib "eagle-import") (part "R_0402"))
    )
    (comp (ref "R28")
      (value "270, 0.5W")
      (footprint "eagle-import:0805")
      (libsource (lib "eagle-import") (part "R_0805"))
    )
    (comp (ref "R29")
      (value "270, 0.5W")
      (footprint "eagle-import:0805")
      (libsource (lib "eagle-import") (part "R_0805"))
    )
    (comp (ref "R30")
      (value "270, 0.5W")
      (footprint "eagle-import:0805")
      (libsource (lib "eagle-import") (part "R_0805"))
    )
    (comp (ref "R31")
      (value "270, 0.5W")
      (footprint "eagle-import:0805")
      (libsource (lib "eagle-import") (part "R_0805"))
    )
    (comp (ref "R32")
      (value "270, 0.5W")
      (footprint "eagle-import:0805")
      (libsource (lib "eagle-import") (part "R_0805"))
    )
    (comp (ref "R33")
      (value "270, 0.5W")
      (footprint "eagle-import:0805")
      (libsource (lib "eagle-import") (part "R_0805"))
    )
    (comp (ref "R34")
      (value "270, 0.5W")
      (footprint "eagle-import:0805")
      (libsource (lib "eagle-import") (part "R_0805"))
    )
    (comp (ref "R35")
      (value "270, 0.5W")
      (footprint "eagle-import:0805")
      (libsource (lib "eagle-import") (part "R_0805"))
    )
    (comp (ref "R36")
      (value "270, 0.5W")
      (footprint "eagle-import:0805")
      (libsource (lib "eagle-import") (part "R_0805"))
    )
    (comp (ref "R37")
      (value "270, 0.5W")
      (footprint "eagle-import:0805")
      (libsource (lib "eagle-import") (part "R_0805"))
    )
    (comp (ref "R38")
      (value "270, 0.5W")
      (footprint "eagle-import:0805")
      (libsource (lib "eagle-import") (part "R_0805"))
    )
    (comp (ref "R39")
      (value "270, 0.5W")
      (footprint "eagle-import:0805")
      (libsource (lib "eagle-import") (part "R_0805"))
    )
    (comp (ref "R40")
      (value "270, 0.5W")
      (footprint "eagle-import:0805")
      (libsource (lib "eagle-import") (part "R_0805"))
    )
    (comp (ref "R41")
      (value "270, 0.5W")
      (footprint "eagle-import:0805")
      (libsource (lib "eagle-import") (part "R_0805"))
    )
    (comp (ref "R42")
      (value "270, 0.5W")
      (footprint "eagle-import:0805")
      (libsource (lib "eagle-import") (part "R_0805"))
    )
    (comp (ref "R43")
      (value "270, 0.5W")
      (footprint "eagle-import:0805")
      (libsource (lib "eagle-import") (part "R_0805"))
    )
    (comp (ref "S1")
      (value "7101J1V3BE2")
      (footprint "eagle-import:CK_7101J1V3QE2")
      (libsource (lib "eagle-import") (part "SPDT_CK-710"))
    )
    (comp (ref "S2")
      (value "7101J1V3BE2")
      (footprint "eagle-import:CK_7101J1V3QE2")
      (libsource (lib "eagle-import") (part "SPDT_CK-710"))
    )
    (comp (ref "S3")
      (value "7101J1V3BE2")
      (footprint "eagle-import:CK_7101J1V3QE2")
      (libsource (lib "eagle-import") (part "SPDT_CK-710"))
    )
    (comp (ref "S4")
      (value "7101J1V3BE2")
      (footprint "eagle-import:CK_7101J1V3QE2")
      (libsource (lib "eagle-import") (part "SPDT_CK-710"))
    )
    (comp (ref "S5")
      (value "CHERRY-MX")
      (footprint "eagle-import:CHERRY-MX")
      (libsource (lib "eagle-import") (part "SPST_TACT2_CHERRY-MX"))
    )
    (comp (ref "S6")
      (value "CHERRY-MX")
      (footprint "eagle-import:CHERRY-MX")
      (libsource (lib "eagle-import") (part "SPST_TACT2_CHERRY-MX"))
    )
    (comp (ref "S7")
      (value "CHERRY-MX")
      (footprint "eagle-import:CHERRY-MX")
      (libsource (lib "eagle-import") (part "SPST_TACT2_CHERRY-MX"))
    )
    (comp (ref "S8")
      (value "CHERRY-MX")
      (footprint "eagle-import:CHERRY-MX")
      (libsource (lib "eagle-import") (part "SPST_TACT2_CHERRY-MX"))
    )
    (comp (ref "S9")
      (value "CHERRY-MX")
      (footprint "eagle-import:CHERRY-MX")
      (libsource (lib "eagle-import") (part "SPST_TACT2_CHERRY-MX"))
    )
    (comp (ref "S10")
      (value "CHERRY-MX")
      (footprint "eagle-import:CHERRY-MX")
      (libsource (lib "eagle-import") (part "SPST_TACT2_CHERRY-MX"))
    )
    (comp (ref "TP1")
      (value "TPTP19R")
      (footprint "eagle-import:TP19R")
      (libsource (lib "eagle-import") (part "TPTP19R"))
    )
    (comp (ref "TP2")
      (value "TPTP19R")
      (footprint "eagle-import:TP19R")
      (libsource (lib "eagle-import") (part "TPTP19R"))
    )
    (comp (ref "TP3")
      (value "TP_2MM")
      (footprint "eagle-import:TESTPOINT_2MM")
      (libsource (lib "eagle-import") (part "TP_2MM"))
    )
    (comp (ref "TP4")
      (value "TP_2MM")
      (footprint "eagle-import:TESTPOINT_2MM")
      (libsource (lib "eagle-import") (part "TP_2MM"))
    )
    (comp (ref "TP5")
      (value "TP_2MM")
      (footprint "eagle-import:TESTPOINT_2MM")
      (libsource (lib "eagle-import") (part "TP_2MM"))
    )
    (comp (ref "TP6")
      (value "TP_2MM")
      (footprint "eagle-import:TESTPOINT_2MM")
      (libsource (lib "eagle-import") (part "TP_2MM"))
    )
    (comp (ref "TP7")
      (value "TP_2MM")
      (footprint "eagle-import:TESTPOINT_2MM")
      (libsource (lib "eagle-import") (part "TP_2MM"))
    )
    (comp (ref "U1")
      (value "SK6805-E-J")
      (footprint "eagle-import:NEOPIXEL-1.5X1.5")
      (libsource (lib "eagle-import") (part "NEOPIXEL_1.5X1.5"))
    )
    (comp (ref "U2")
      (value "SK6805-E-J")
      (footprint "eagle-import:NEOPIXEL-1.5X1.5")
      (libsource (lib "eagle-import") (part "NEOPIXEL_1.5X1.5"))
    )
    (comp (ref "U3")
      (value "SK6805-E-J")
      (footprint "eagle-import:NEOPIXEL-1.5X1.5")
      (libsource (lib "eagle-import") (part "NEOPIXEL_1.5X1.5"))
    )
    (comp (ref "U4")
      (value "SK6805-E-J")
      (footprint "eagle-import:NEOPIXEL-1.5X1.5")
      (libsource (lib "eagle-import") (part "NEOPIXEL_1.5X1.5"))
    )
    (comp (ref "U5")
      (value "SK6805-E-J")
      (footprint "eagle-import:NEOPIXEL-1.5X1.5")
      (libsource (lib "eagle-import") (part "NEOPIXEL_1.5X1.5"))
    )
    (comp (ref "U6")
      (value "SK6805-E-J")
      (footprint "eagle-import:NEOPIXEL-1.5X1.5")
      (libsource (lib "eagle-import") (part "NEOPIXEL_1.5X1.5"))
    )
    (comp (ref "U7")
      (value "SK6805-E-J")
      (footprint "eagle-import:NEOPIXEL-1.5X1.5")
      (libsource (lib "eagle-import") (part "NEOPIXEL_1.5X1.5"))
    )
    (comp (ref "U8")
      (value "SK6805-E-J")
      (footprint "eagle-import:NEOPIXEL-1.5X1.5")
      (libsource (lib "eagle-import") (part "NEOPIXEL_1.5X1.5"))
    )
    (comp (ref "U9")
      (value "SK6805-E-J")
      (footprint "eagle-import:NEOPIXEL-1.5X1.5")
      (libsource (lib "eagle-import") (part "NEOPIXEL_1.5X1.5"))
    )
    (comp (ref "U10")
      (value "TXB0101")
      (footprint "eagle-import:SOT23-6")
      (libsource (lib "eagle-import") (part "LEVEL_SHIFTER_SOT23"))
    )
    (comp (ref "U11")
      (value "SK6805-E-J")
      (footprint "eagle-import:NEOPIXEL-1.5X1.5")
      (libsource (lib "eagle-import") (part "NEOPIXEL_1.5X1.5"))
    )
    (comp (ref "U12")
      (value "SK6805-E-J")
      (footprint "eagle-import:NEOPIXEL-1.5X1.5")
      (libsource (lib "eagle-import") (part "NEOPIXEL_1.5X1.5"))
    )
    (comp (ref "U13")
      (value "SK6805-E-J")
      (footprint "eagle-import:NEOPIXEL-1.5X1.5")
      (libsource (lib "eagle-import") (part "NEOPIXEL_1.5X1.5"))
    )
    (comp (ref "U14")
      (value "SK6805-E-J")
      (footprint "eagle-import:NEOPIXEL-1.5X1.5")
      (libsource (lib "eagle-import") (part "NEOPIXEL_1.5X1.5"))
    )
    (comp (ref "U15")
      (value "SK6805-E-J")
      (footprint "eagle-import:NEOPIXEL-1.5X1.5")
      (libsource (lib "eagle-import") (part "NEOPIXEL_1.5X1.5"))
    )
    (comp (ref "U16")
      (value "SK6805-E-J")
      (footprint "eagle-import:NEOPIXEL-1.5X1.5")
      (libsource (lib "eagle-import") (part "NEOPIXEL_1.5X1.5"))
    )
    (comp (ref "U17")
      (value "SK6805-E-J")
      (footprint "eagle-import:NEOPIXEL-1.5X1.5")
      (libsource (lib "eagle-import") (part "NEOPIXEL_1.5X1.5"))
    )
    (comp (ref "U18")
      (value "SK6805-E-J")
      (footprint "eagle-import:NEOPIXEL-1.5X1.5")
      (libsource (lib "eagle-import") (part "NEOPIXEL_1.5X1.5"))
    )
    (comp (ref "U19")
      (value "SK6805-E-J")
      (footprint "eagle-import:NEOPIXEL-1.5X1.5")
      (libsource (lib "eagle-import") (part "NEOPIXEL_1.5X1.5"))
    )
    (comp (ref "U20")
      (value "SK6805-E-J")
      (footprint "eagle-import:NEOPIXEL-1.5X1.5")
      (libsource (lib "eagle-import") (part "NEOPIXEL_1.5X1.5"))
    )
    (comp (ref "U21")
      (value "SK6805-E-J")
      (footprint "eagle-import:NEOPIXEL-1.5X1.5")
      (libsource (lib "eagle-import") (part "NEOPIXEL_1.5X1.5"))
    )
    (comp (ref "U22")
      (value "SK6805-E-J")
      (footprint "eagle-import:NEOPIXEL-1.5X1.5")
      (libsource (lib "eagle-import") (part "NEOPIXEL_1.5X1.5"))
    )
    (comp (ref "U23")
      (value "SK6805-E-J")
      (footprint "eagle-import:NEOPIXEL-1.5X1.5")
      (libsource (lib "eagle-import") (part "NEOPIXEL_1.5X1.5"))
    )
    (comp (ref "U24")
      (value "SK6805-E-J")
      (footprint "eagle-import:NEOPIXEL-1.5X1.5")
      (libsource (lib "eagle-import") (part "NEOPIXEL_1.5X1.5"))
    )
    (comp (ref "U25")
      (value "SK6805-E-J")
      (footprint "eagle-import:NEOPIXEL-1.5X1.5")
      (libsource (lib "eagle-import") (part "NEOPIXEL_1.5X1.5"))
    )
    (comp (ref "U26")
      (value "SK6805-E-J")
      (footprint "eagle-import:NEOPIXEL-1.5X1.5")
      (libsource (lib "eagle-import") (part "NEOPIXEL_1.5X1.5"))
    )
    (comp (ref "U27")
      (value "SK6805-E-J")
      (footprint "eagle-import:NEOPIXEL-1.5X1.5")
      (libsource (lib "eagle-import") (part "NEOPIXEL_1.5X1.5"))
    )
    (comp (ref "U28")
      (value "SK6805-E-J")
      (footprint "eagle-import:NEOPIXEL-1.5X1.5")
      (libsource (lib "eagle-import") (part "NEOPIXEL_1.5X1.5"))
    )
    (comp (ref "U29")
      (value "SK6805-E-J")
      (footprint "eagle-import:NEOPIXEL-1.5X1.5")
      (libsource (lib "eagle-import") (part "NEOPIXEL_1.5X1.5"))
    )
    (comp (ref "U30")
      (value "SK6805-E-J")
      (footprint "eagle-import:NEOPIXEL-1.5X1.5")
      (libsource (lib "eagle-import") (part "NEOPIXEL_1.5X1.5"))
    )
    (comp (ref "U31")
      (value "SK6805-E-J")
      (footprint "eagle-import:NEOPIXEL-1.5X1.5")
      (libsource (lib "eagle-import") (part "NEOPIXEL_1.5X1.5"))
    )
    (comp (ref "U32")
      (value "SK6805-E-J")
      (footprint "eagle-import:NEOPIXEL-1.5X1.5")
      (libsource (lib "eagle-import") (part "NEOPIXEL_1.5X1.5"))
    )
    (comp (ref "U33")
      (value "SK6805-E-J")
      (footprint "eagle-import:NEOPIXEL-1.5X1.5")
      (libsource (lib "eagle-import") (part "NEOPIXEL_1.5X1.5"))
    )
    (comp (ref "U34")
      (value "SK6805-E-J")
      (footprint "eagle-import:NEOPIXEL-1.5X1.5")
      (libsource (lib "eagle-import") (part "NEOPIXEL_1.5X1.5"))
    )
    (comp (ref "U35")
      (value "SK6805-E-J")
      (footprint "eagle-import:NEOPIXEL-1.5X1.5")
      (libsource (lib "eagle-import") (part "NEOPIXEL_1.5X1.5"))
    )
    (comp (ref "U36")
      (value "SK6805-E-J")
      (footprint "eagle-import:NEOPIXEL-1.5X1.5")
      (libsource (lib "eagle-import") (part "NEOPIXEL_1.5X1.5"))
    )
    (comp (ref "U37")
      (value "SK6805-E-J")
      (footprint "eagle-import:NEOPIXEL-1.5X1.5")
      (libsource (lib "eagle-import") (part "NEOPIXEL_1.5X1.5"))
    )
    (comp (ref "U38")
      (value "SK6805-E-J")
      (footprint "eagle-import:NEOPIXEL-1.5X1.5")
      (libsource (lib "eagle-import") (part "NEOPIXEL_1.5X1.5"))
    )
    (comp (ref "U39")
      (value "SK6805-E-J")
      (footprint "eagle-import:NEOPIXEL-1.5X1.5")
      (libsource (lib "eagle-import") (part "NEOPIXEL_1.5X1.5"))
    )
    (comp (ref "U40")
      (value "SK6805-E-J")
      (footprint "eagle-import:NEOPIXEL-1.5X1.5")
      (libsource (lib "eagle-import") (part "NEOPIXEL_1.5X1.5"))
    )
    (comp (ref "U41")
      (value "SK6805-E-J")
      (footprint "eagle-import:NEOPIXEL-1.5X1.5")
      (libsource (lib "eagle-import") (part "NEOPIXEL_1.5X1.5"))
    )
    (comp (ref "U42")
      (value "SK6805-E-J")
      (footprint "eagle-import:NEOPIXEL-1.5X1.5")
      (libsource (lib "eagle-import") (part "NEOPIXEL_1.5X1.5"))
    )
    (comp (ref "U43")
      (value "G6K-2F-RF")
      (footprint "eagle-import:G6KU-2F-RF")
      (libsource (lib "eagle-import") (part "G6KU-2F-RF-TR09DC5"))
    )
    (comp (ref "U44")
      (value "G6K-2F-RF")
      (footprint "eagle-import:G6KU-2F-RF")
      (libsource (lib "eagle-import") (part "G6KU-2F-RF-TR09DC5"))
    )
    (comp (ref "U45")
      (value "G6K-2F-RF")
      (footprint "eagle-import:G6KU-2F-RF")
      (libsource (lib "eagle-import") (part "G6KU-2F-RF-TR09DC5"))
    )
    (comp (ref "U46")
      (value "G6K-2F-RF")
      (footprint "eagle-import:G6KU-2F-RF")
      (libsource (lib "eagle-import") (part "G6KU-2F-RF-TR09DC5"))
    )
    (comp (ref "U47")
      (value "LTM4622A")
      (footprint "eagle-import:BGA_5X5_625X625")
      (libsource (lib "eagle-import") (part "LTM4622_BGA"))
    )
    (comp (ref "U48")
      (value "SI8610")
      (footprint "eagle-import:SO-08")
      (libsource (lib "eagle-import") (part "SI8610"))
    )
    (comp (ref "U49")
      (value "TINY-FPGA-BX")
      (footprint "eagle-import:TINY-FPGA-BX_BASIC")
      (libsource (lib "eagle-import") (part "TINY-FPGA-BX_BASIC"))
    )
    (comp (ref "U50")
      (value "TCA9555")
      (footprint "eagle-import:TSSOP-24")
      (libsource (lib "eagle-import") (part "TCA9555"))
    )
    (comp (ref "U51")
      (value "FIN1032MTCX")
      (footprint "eagle-import:TSSOP-16")
      (libsource (lib "eagle-import") (part "LVDS_RECEIVER_QUAD_TSSOP"))
    )
    (comp (ref "U52")
      (value "SN65LVDS9638DGN")
      (footprint "eagle-import:MSOP-8-PAD-3X3")
      (libsource (lib "eagle-import") (part "LVDS_DRIVER_DUAL_MSOP"))
    )
    (comp (ref "U53")
      (value "SN65LVDS9638DGN")
      (footprint "eagle-import:MSOP-8-PAD-3X3")
      (libsource (lib "eagle-import") (part "LVDS_DRIVER_DUAL_MSOP"))
    )
    (comp (ref "X")
      (value "OE-LOGO_28X20")
      (footprint "eagle-import:OE-LOGO-28X20")
      (libsource (lib "eagle-import") (part "OE-LOGO_28X20"))
    )
  )
  (nets
    (net (code "1") (name "+3V3") (class "Default")
      (node (ref "C1") (pin "1") (pinfunction "1_1") (pintype "passive"))
      (node (ref "C37") (pin "2") (pinfunction "2_2") (pintype "passive"))
      (node (ref "C42") (pin "2") (pinfunction "2_2") (pintype "passive"))
      (node (ref "C44") (pin "1") (pinfunction "1_1") (pintype "passive"))
      (node (ref "C45") (pin "1") (pinfunction "1_1") (pintype "passive"))
      (node (ref "C46") (pin "1") (pinfunction "1_1") (pintype "passive"))
      (node (ref "C47") (pin "1") (pinfunction "1_1") (pintype "passive"))
      (node (ref "C48") (pin "1") (pinfunction "1_1") (pintype "passive"))
      (node (ref "C49") (pin "1") (pinfunction "1_1") (pintype "passive"))
      (node (ref "D17") (pin "2") (pinfunction "C_2") (pintype "passive"))
      (node (ref "D18") (pin "2") (pinfunction "C_2") (pintype "passive"))
      (node (ref "D19") (pin "2") (pinfunction "C_2") (pintype "passive"))
      (node (ref "D20") (pin "2") (pinfunction "C_2") (pintype "passive"))
      (node (ref "D21") (pin "8") (pinfunction "VCC_8") (pintype "power_in"))
      (node (ref "D22") (pin "2") (pinfunction "C_2") (pintype "passive"))
      (node (ref "D23") (pin "2") (pinfunction "C_2") (pintype "passive"))
      (node (ref "D24") (pin "2") (pinfunction "C_2") (pintype "passive"))
      (node (ref "D25") (pin "2") (pinfunction "C_2") (pintype "passive"))
      (node (ref "D26") (pin "2") (pinfunction "C_2") (pintype "passive"))
      (node (ref "D27") (pin "2") (pinfunction "C_2") (pintype "passive"))
      (node (ref "D28") (pin "2") (pinfunction "C_2") (pintype "passive"))
      (node (ref "D29") (pin "2") (pinfunction "C_2") (pintype "passive"))
      (node (ref "D30") (pin "8") (pinfunction "VCC_8") (pintype "power_in"))
      (node (ref "D31") (pin "2") (pinfunction "C_2") (pintype "passive"))
      (node (ref "D32") (pin "2") (pinfunction "C_2") (pintype "passive"))
      (node (ref "D33") (pin "2") (pinfunction "C_2") (pintype "passive"))
      (node (ref "D34") (pin "2") (pinfunction "C_2") (pintype "passive"))
      (node (ref "R2") (pin "1") (pinfunction "1_1") (pintype "passive"))
      (node (ref "R22") (pin "1") (pinfunction "1_1") (pintype "passive"))
      (node (ref "R23") (pin "1") (pinfunction "1_1") (pintype "passive"))
      (node (ref "R24") (pin "1") (pinfunction "1_1") (pintype "passive"))
      (node (ref "TP1") (pin "TP") (pinfunction "TP_TP") (pintype "bidirectional"))
      (node (ref "U10") (pin "1") (pinfunction "VCCA_1") (pintype "power_in"))
      (node (ref "U47") (pin "D1") (pinfunction "VOUT1_D1") (pintype "power_in"))
      (node (ref "U47") (pin "E1") (pinfunction "VOUT1_E1") (pintype "power_in"))
      (node (ref "U50") (pin "24") (pinfunction "VCC_24") (pintype "bidirectional"))
      (node (ref "U51") (pin "16") (pinfunction "VCC_16") (pintype "power_in"))
      (node (ref "U51") (pin "4") (pinfunction "EN_4") (pintype "input"))
      (node (ref "U52") (pin "1") (pinfunction "VCC_1") (pintype "power_in"))
      (node (ref "U53") (pin "1") (pinfunction "VCC_1") (pintype "power_in"))
    )
    (net (code "2") (name "+5V") (class "Default")
      (node (ref "C10") (pin "2") (pinfunction "2_2") (pintype "passive"))
      (node (ref "C11") (pin "2") (pinfunction "2_2") (pintype "passive"))
      (node (ref "C12") (pin "2") (pinfunction "2_2") (pintype "passive"))
      (node (ref "C13") (pin "2") (pinfunction "2_2") (pintype "passive"))
      (node (ref "C14") (pin "2") (pinfunction "2_2") (pintype "passive"))
      (node (ref "C15") (pin "2") (pinfunction "2_2") (pintype "passive"))
      (node (ref "C16") (pin "2") (pinfunction "2_2") (pintype "passive"))
      (node (ref "C17") (pin "2") (pinfunction "2_2") (pintype "passive"))
      (node (ref "C18") (pin "2") (pinfunction "2_2") (pintype "passive"))
      (node (ref "C19") (pin "2") (pinfunction "2_2") (pintype "passive"))
      (node (ref "C2") (pin "1") (pinfunction "1_1") (pintype "passive"))
      (node (ref "C20") (pin "2") (pinfunction "2_2") (pintype "passive"))
      (node (ref "C21") (pin "2") (pinfunction "2_2") (pintype "passive"))
      (node (ref "C22") (pin "2") (pinfunction "2_2") (pintype "passive"))
      (node (ref "C23") (pin "2") (pinfunction "2_2") (pintype "passive"))
      (node (ref "C24") (pin "2") (pinfunction "2_2") (pintype "passive"))
      (node (ref "C25") (pin "2") (pinfunction "2_2") (pintype "passive"))
      (node (ref "C26") (pin "2") (pinfunction "2_2") (pintype "passive"))
      (node (ref "C27") (pin "2") (pinfunction "2_2") (pintype "passive"))
      (node (ref "C3") (pin "2") (pinfunction "2_2") (pintype "passive"))
      (node (ref "C36") (pin "2") (pinfunction "2_2") (pintype "passive"))
      (node (ref "C4") (pin "2") (pinfunction "2_2") (pintype "passive"))
      (node (ref "C43") (pin "2") (pinfunction "2_2") (pintype "passive"))
      (node (ref "C5") (pin "2") (pinfunction "2_2") (pintype "passive"))
      (node (ref "C6") (pin "2") (pinfunction "2_2") (pintype "passive"))
      (node (ref "C7") (pin "2") (pinfunction "2_2") (pintype "passive"))
      (node (ref "C8") (pin "2") (pinfunction "2_2") (pintype "passive"))
      (node (ref "C9") (pin "2") (pinfunction "2_2") (pintype "passive"))
      (node (ref "D1") (pin "C") (pinfunction "C_C") (pintype "passive"))
      (node (ref "D2") (pin "C") (pinfunction "C_C") (pintype "passive"))
      (node (ref "D3") (pin "C") (pinfunction "C_C") (pintype "passive"))
      (node (ref "D4") (pin "C") (pinfunction "C_C") (pintype "passive"))
      (node (ref "Q9") (pin "D") (pinfunction "D_D") (pintype "bidirectional"))
      (node (ref "S1") (pin "3") (pinfunction "3_3") (pintype "passive"))
      (node (ref "S2") (pin "3") (pinfunction "3_3") (pintype "passive"))
      (node (ref "S3") (pin "3") (pinfunction "3_3") (pintype "passive"))
      (node (ref "S4") (pin "3") (pinfunction "3_3") (pintype "passive"))
      (node (ref "TP2") (pin "TP") (pinfunction "TP_TP") (pintype "bidirectional"))
      (node (ref "U1") (pin "2") (pinfunction "VDD_2") (pintype "power_in"))
      (node (ref "U10") (pin "6") (pinfunction "VCCB_6") (pintype "power_in"))
      (node (ref "U11") (pin "2") (pinfunction "VDD_2") (pintype "power_in"))
      (node (ref "U12") (pin "2") (pinfunction "VDD_2") (pintype "power_in"))
      (node (ref "U13") (pin "2") (pinfunction "VDD_2") (pintype "power_in"))
      (node (ref "U14") (pin "2") (pinfunction "VDD_2") (pintype "power_in"))
      (node (ref "U15") (pin "2") (pinfunction "VDD_2") (pintype "power_in"))
      (node (ref "U16") (pin "2") (pinfunction "VDD_2") (pintype "power_in"))
      (node (ref "U17") (pin "2") (pinfunction "VDD_2") (pintype "power_in"))
      (node (ref "U18") (pin "2") (pinfunction "VDD_2") (pintype "power_in"))
      (node (ref "U19") (pin "2") (pinfunction "VDD_2") (pintype "power_in"))
      (node (ref "U2") (pin "2") (pinfunction "VDD_2") (pintype "power_in"))
      (node (ref "U20") (pin "2") (pinfunction "VDD_2") (pintype "power_in"))
      (node (ref "U21") (pin "2") (pinfunction "VDD_2") (pintype "power_in"))
      (node (ref "U22") (pin "2") (pinfunction "VDD_2") (pintype "power_in"))
      (node (ref "U23") (pin "2") (pinfunction "VDD_2") (pintype "power_in"))
      (node (ref "U24") (pin "2") (pinfunction "VDD_2") (pintype "power_in"))
      (node (ref "U25") (pin "2") (pinfunction "VDD_2") (pintype "power_in"))
      (node (ref "U26") (pin "2") (pinfunction "VDD_2") (pintype "power_in"))
      (node (ref "U27") (pin "2") (pinfunction "VDD_2") (pintype "power_in"))
      (node (ref "U28") (pin "2") (pinfunction "VDD_2") (pintype "power_in"))
      (node (ref "U29") (pin "2") (pinfunction "VDD_2") (pintype "power_in"))
      (node (ref "U3") (pin "2") (pinfunction "VDD_2") (pintype "power_in"))
      (node (ref "U30") (pin "2") (pinfunction "VDD_2") (pintype "power_in"))
      (node (ref "U31") (pin "2") (pinfunction "VDD_2") (pintype "power_in"))
      (node (ref "U32") (pin "2") (pinfunction "VDD_2") (pintype "power_in"))
      (node (ref "U33") (pin "2") (pinfunction "VDD_2") (pintype "power_in"))
      (node (ref "U34") (pin "2") (pinfunction "VDD_2") (pintype "power_in"))
      (node (ref "U35") (pin "2") (pinfunction "VDD_2") (pintype "power_in"))
      (node (ref "U36") (pin "2") (pinfunction "VDD_2") (pintype "power_in"))
      (node (ref "U37") (pin "2") (pinfunction "VDD_2") (pintype "power_in"))
      (node (ref "U38") (pin "2") (pinfunction "VDD_2") (pintype "power_in"))
      (node (ref "U39") (pin "2") (pinfunction "VDD_2") (pintype "power_in"))
      (node (ref "U4") (pin "2") (pinfunction "VDD_2") (pintype "power_in"))
      (node (ref "U40") (pin "2") (pinfunction "VDD_2") (pintype "power_in"))
      (node (ref "U41") (pin "2") (pinfunction "VDD_2") (pintype "power_in"))
      (node (ref "U42") (pin "2") (pinfunction "VDD_2") (pintype "power_in"))
      (node (ref "U43") (pin "1") (pinfunction "COIL+_1") (pintype "bidirectional"))
      (node (ref "U44") (pin "1") (pinfunction "COIL+_1") (pintype "bidirectional"))
      (node (ref "U45") (pin "1") (pinfunction "COIL+_1") (pintype "bidirectional"))
      (node (ref "U46") (pin "1") (pinfunction "COIL+_1") (pintype "bidirectional"))
      (node (ref "U47") (pin "A1") (pinfunction "VOUT2_A1") (pintype "power_in"))
      (node (ref "U47") (pin "B1") (pinfunction "VOUT2_B1") (pintype "power_in"))
      (node (ref "U48") (pin "1") (pinfunction "AVDD_1") (pintype "bidirectional"))
      (node (ref "U5") (pin "2") (pinfunction "VDD_2") (pintype "power_in"))
      (node (ref "U6") (pin "2") (pinfunction "VDD_2") (pintype "power_in"))
      (node (ref "U7") (pin "2") (pinfunction "VDD_2") (pintype "power_in"))
      (node (ref "U8") (pin "2") (pinfunction "VDD_2") (pintype "power_in"))
      (node (ref "U9") (pin "2") (pinfunction "VDD_2") (pintype "power_in"))
    )
    (net (code "3") (name "+5V0_GOOD") (class "Default")
      (node (ref "Q9") (pin "G") (pinfunction "G_G") (pintype "bidirectional"))
      (node (ref "R25") (pin "1") (pinfunction "1_1") (pintype "passive"))
      (node (ref "U47") (pin "B4") (pinfunction "PGOOD2_B4") (pintype "open_collector"))
    )
    (net (code "4") (name "+12V") (class "Default")
      (node (ref "C40") (pin "2") (pinfunction "2_2") (pintype "passive"))
      (node (ref "J32") (pin "1") (pinfunction "1_1") (pintype "bidirectional"))
      (node (ref "J32") (pin "26") (pinfunction "26_26") (pintype "bidirectional"))
      (node (ref "R25") (pin "2") (pinfunction "2_2") (pintype "passive"))
      (node (ref "TP7") (pin "1") (pinfunction "TP_1") (pintype "bidirectional"))
      (node (ref "U47") (pin "A2") (pinfunction "VIN_A2") (pintype "power_in"))
      (node (ref "U47") (pin "B2") (pinfunction "RUN2_B2") (pintype "input"))
      (node (ref "U47") (pin "B3") (pinfunction "VIN_B3") (pintype "power_in"))
      (node (ref "U47") (pin "D2") (pinfunction "RUN1_D2") (pintype "input"))
      (node (ref "U47") (pin "D3") (pinfunction "VIN_D3") (pintype "power_in"))
      (node (ref "U47") (pin "E2") (pinfunction "VIN_E2") (pintype "power_in"))
    )
    (net (code "5") (name "/3.3V") (class "Default")
      (node (ref "U49") (pin "3.3V") (pinfunction "3.3V_3.3V") (pintype "power_in"))
    )
    (net (code "6") (name "/LVDS_DIN0_N") (class "Default")
      (node (ref "J32") (pin "23") (pinfunction "23_23") (pintype "bidirectional"))
      (node (ref "U52") (pin "5") (pinfunction "BOUT-_5") (pintype "output"))
    )
    (net (code "7") (name "/LVDS_DIN0_P") (class "Default")
      (node (ref "J32") (pin "10") (pinfunction "10_10") (pintype "bidirectional"))
      (node (ref "U52") (pin "6") (pinfunction "BOUT+_6") (pintype "output"))
    )
    (net (code "8") (name "/LVDS_DIN1_N") (class "Default")
      (node (ref "J32") (pin "11") (pinfunction "11_11") (pintype "bidirectional"))
      (node (ref "U52") (pin "7") (pinfunction "AOUT-_7") (pintype "output"))
    )
    (net (code "9") (name "/LVDS_DIN1_P") (class "Default")
      (node (ref "J32") (pin "24") (pinfunction "24_24") (pintype "bidirectional"))
      (node (ref "U52") (pin "8") (pinfunction "AOUT+_8") (pintype "output"))
    )
    (net (code "10") (name "/LVDS_DIN2_N") (class "Default")
      (node (ref "J32") (pin "25") (pinfunction "25_25") (pintype "bidirectional"))
      (node (ref "U53") (pin "7") (pinfunction "AOUT-_7") (pintype "output"))
    )
    (net (code "11") (name "/LVDS_DIN2_P") (class "Default")
      (node (ref "J32") (pin "12") (pinfunction "12_12") (pintype "bidirectional"))
      (node (ref "U53") (pin "8") (pinfunction "AOUT+_8") (pintype "output"))
    )
    (net (code "12") (name "/LVDS_DOUT0_N") (class "Default")
      (node (ref "J32") (pin "8") (pinfunction "8_8") (pintype "bidirectional"))
      (node (ref "R26") (pin "1") (pinfunction "1_1") (pintype "passive"))
      (node (ref "U51") (pin "1") (pinfunction "A-_1") (pintype "input"))
    )
    (net (code "13") (name "/LVDS_DOUT0_P") (class "Default")
      (node (ref "J32") (pin "21") (pinfunction "21_21") (pintype "bidirectional"))
      (node (ref "R26") (pin "2") (pinfunction "2_2") (pintype "passive"))
      (node (ref "U51") (pin "2") (pinfunction "A+_2") (pintype "input"))
    )
    (net (code "14") (name "/LVDS_DOUT1_N") (class "Default")
      (node (ref "J32") (pin "9") (pinfunction "9_9") (pintype "bidirectional"))
      (node (ref "R27") (pin "1") (pinfunction "1_1") (pintype "passive"))
      (node (ref "U51") (pin "7") (pinfunction "B-_7") (pintype "input"))
    )
    (net (code "15") (name "/LVDS_DOUT1_P") (class "Default")
      (node (ref "J32") (pin "22") (pinfunction "22_22") (pintype "bidirectional"))
      (node (ref "R27") (pin "2") (pinfunction "2_2") (pintype "passive"))
      (node (ref "U51") (pin "6") (pinfunction "B+_6") (pintype "input"))
    )
    (net (code "16") (name "/~{TCA_INT}") (class "Default")
      (node (ref "R22") (pin "2") (pinfunction "2_2") (pintype "passive"))
      (node (ref "U50") (pin "1") (pinfunction "_INT_1") (pintype "bidirectional"))
    )
    (net (code "17") (name "AGND") (class "Default")
      (node (ref "D10") (pin "A") (pinfunction "1_A") (pintype "passive"))
      (node (ref "D11") (pin "A") (pinfunction "1_A") (pintype "passive"))
      (node (ref "D12") (pin "A") (pinfunction "1_A") (pintype "passive"))
      (node (ref "D13") (pin "A") (pinfunction "1_A") (pintype "passive"))
      (node (ref "D14") (pin "A") (pinfunction "1_A") (pintype "passive"))
      (node (ref "D15") (pin "A") (pinfunction "1_A") (pintype "passive"))
      (node (ref "D16") (pin "A") (pinfunction "1_A") (pintype "passive"))
      (node (ref "D5") (pin "A") (pinfunction "1_A") (pintype "passive"))
      (node (ref "D6") (pin "A") (pinfunction "1_A") (pintype "passive"))
      (node (ref "D7") (pin "A") (pinfunction "1_A") (pintype "passive"))
      (node (ref "D8") (pin "A") (pinfunction "1_A") (pintype "passive"))
      (node (ref "D9") (pin "A") (pinfunction "1_A") (pintype "passive"))
      (node (ref "J10") (pin "2") (pinfunction "2_2") (pintype "passive"))
      (node (ref "J10") (pin "3") (pinfunction "2_3") (pintype "passive"))
      (node (ref "J10") (pin "4") (pinfunction "2_4") (pintype "passive"))
      (node (ref "J10") (pin "5") (pinfunction "2_5") (pintype "passive"))
      (node (ref "J11") (pin "2") (pinfunction "2_2") (pintype "passive"))
      (node (ref "J11") (pin "3") (pinfunction "2_3") (pintype "passive"))
      (node (ref "J11") (pin "4") (pinfunction "2_4") (pintype "passive"))
      (node (ref "J11") (pin "5") (pinfunction "2_5") (pintype "passive"))
      (node (ref "J12") (pin "2") (pinfunction "2_2") (pintype "passive"))
      (node (ref "J12") (pin "3") (pinfunction "2_3") (pintype "passive"))
      (node (ref "J12") (pin "4") (pinfunction "2_4") (pintype "passive"))
      (node (ref "J12") (pin "5") (pinfunction "2_5") (pintype "passive"))
      (node (ref "J13") (pin "2") (pinfunction "2_2") (pintype "passive"))
      (node (ref "J13") (pin "3") (pinfunction "2_3") (pintype "passive"))
      (node (ref "J13") (pin "4") (pinfunction "2_4") (pintype "passive"))
      (node (ref "J13") (pin "5") (pinfunction "2_5") (pintype "passive"))
      (node (ref "J14") (pin "2") (pinfunction "2_2") (pintype "passive"))
      (node (ref "J14") (pin "3") (pinfunction "2_3") (pintype "passive"))
      (node (ref "J14") (pin "4") (pinfunction "2_4") (pintype "passive"))
      (node (ref "J14") (pin "5") (pinfunction "2_5") (pintype "passive"))
      (node (ref "J17") (pin "1") (pinfunction "1_1") (pintype "passive"))
      (node (ref "J17") (pin "15") (pinfunction "15_15") (pintype "passive"))
      (node (ref "J17") (pin "16") (pinfunction "16_16") (pintype "passive"))
      (node (ref "J17") (pin "17") (pinfunction "1_17") (pintype "passive"))
      (node (ref "J17") (pin "18") (pinfunction "2_18") (pintype "passive"))
      (node (ref "J17") (pin "2") (pinfunction "2_2") (pintype "passive"))
      (node (ref "J17") (pin "31") (pinfunction "15_31") (pintype "passive"))
      (node (ref "J17") (pin "32") (pinfunction "16_32") (pintype "passive"))
      (node (ref "J20") (pin "2") (pinfunction "2_2") (pintype "passive"))
      (node (ref "J20") (pin "3") (pinfunction "2_3") (pintype "passive"))
      (node (ref "J20") (pin "4") (pinfunction "2_4") (pintype "passive"))
      (node (ref "J20") (pin "5") (pinfunction "2_5") (pintype "passive"))
      (node (ref "J21") (pin "2") (pinfunction "2_2") (pintype "passive"))
      (node (ref "J21") (pin "3") (pinfunction "2_3") (pintype "passive"))
      (node (ref "J21") (pin "4") (pinfunction "2_4") (pintype "passive"))
      (node (ref "J21") (pin "5") (pinfunction "2_5") (pintype "passive"))
      (node (ref "J22") (pin "2") (pinfunction "2_2") (pintype "passive"))
      (node (ref "J22") (pin "3") (pinfunction "2_3") (pintype "passive"))
      (node (ref "J22") (pin "4") (pinfunction "2_4") (pintype "passive"))
      (node (ref "J22") (pin "5") (pinfunction "2_5") (pintype "passive"))
      (node (ref "J23") (pin "2") (pinfunction "2_2") (pintype "passive"))
      (node (ref "J23") (pin "3") (pinfunction "2_3") (pintype "passive"))
      (node (ref "J23") (pin "4") (pinfunction "2_4") (pintype "passive"))
      (node (ref "J23") (pin "5") (pinfunction "2_5") (pintype "passive"))
      (node (ref "J24") (pin "2") (pinfunction "2_2") (pintype "passive"))
      (node (ref "J24") (pin "3") (pinfunction "2_3") (pintype "passive"))
      (node (ref "J24") (pin "4") (pinfunction "2_4") (pintype "passive"))
      (node (ref "J24") (pin "5") (pinfunction "2_5") (pintype "passive"))
      (node (ref "J25") (pin "2") (pinfunction "2_2") (pintype "passive"))
      (node (ref "J25") (pin "3") (pinfunction "2_3") (pintype "passive"))
      (node (ref "J25") (pin "4") (pinfunction "2_4") (pintype "passive"))
      (node (ref "J25") (pin "5") (pinfunction "2_5") (pintype "passive"))
      (node (ref "J26") (pin "1") (pinfunction "1_1") (pintype "bidirectional"))
      (node (ref "J26") (pin "11") (pinfunction "11_11") (pintype "bidirectional"))
      (node (ref "J26") (pin "13") (pinfunction "13_13") (pintype "bidirectional"))
      (node (ref "J26") (pin "15") (pinfunction "15_15") (pintype "bidirectional"))
      (node (ref "J26") (pin "17") (pinfunction "17_17") (pintype "bidirectional"))
      (node (ref "J26") (pin "19") (pinfunction "19_19") (pintype "bidirectional"))
      (node (ref "J26") (pin "21") (pinfunction "21_21") (pintype "bidirectional"))
      (node (ref "J26") (pin "23") (pinfunction "23_23") (pintype "bidirectional"))
      (node (ref "J26") (pin "3") (pinfunction "3_3") (pintype "bidirectional"))
      (node (ref "J26") (pin "5") (pinfunction "5_5") (pintype "bidirectional"))
      (node (ref "J26") (pin "7") (pinfunction "7_7") (pintype "bidirectional"))
      (node (ref "J26") (pin "9") (pinfunction "9_9") (pintype "bidirectional"))
      (node (ref "J32") (pin "13") (pinfunction "13_13") (pintype "bidirectional"))
      (node (ref "J32") (pin "14") (pinfunction "14_14") (pintype "bidirectional"))
      (node (ref "J9") (pin "2") (pinfunction "2_2") (pintype "passive"))
      (node (ref "J9") (pin "3") (pinfunction "2_3") (pintype "passive"))
      (node (ref "J9") (pin "4") (pinfunction "2_4") (pintype "passive"))
      (node (ref "J9") (pin "5") (pinfunction "2_5") (pintype "passive"))
      (node (ref "TP6") (pin "1") (pinfunction "TP_1") (pintype "bidirectional"))
    )
    (net (code "18") (name "AIO_0") (class "Default")
      (node (ref "D5") (pin "C") (pinfunction "2_C") (pintype "passive"))
      (node (ref "J17") (pin "19") (pinfunction "3_19") (pintype "passive"))
      (node (ref "J17") (pin "3") (pinfunction "3_3") (pintype "passive"))
      (node (ref "J26") (pin "2") (pinfunction "2_2") (pintype "bidirectional"))
      (node (ref "J32") (pin "20") (pinfunction "20_20") (pintype "bidirectional"))
      (node (ref "J9") (pin "1") (pinfunction "1_1") (pintype "passive"))
    )
    (net (code "19") (name "AIO_1") (class "Default")
      (node (ref "D6") (pin "C") (pinfunction "2_C") (pintype "passive"))
      (node (ref "J10") (pin "1") (pinfunction "1_1") (pintype "passive"))
      (node (ref "J17") (pin "20") (pinfunction "4_20") (pintype "passive"))
      (node (ref "J17") (pin "4") (pinfunction "4_4") (pintype "passive"))
      (node (ref "J26") (pin "4") (pinfunction "4_4") (pintype "bidirectional"))
      (node (ref "J32") (pin "7") (pinfunction "7_7") (pintype "bidirectional"))
    )
    (net (code "20") (name "AIO_2") (class "Default")
      (node (ref "D7") (pin "C") (pinfunction "2_C") (pintype "passive"))
      (node (ref "J11") (pin "1") (pinfunction "1_1") (pintype "passive"))
      (node (ref "J17") (pin "21") (pinfunction "5_21") (pintype "passive"))
      (node (ref "J17") (pin "5") (pinfunction "5_5") (pintype "passive"))
      (node (ref "J26") (pin "6") (pinfunction "6_6") (pintype "bidirectional"))
      (node (ref "J32") (pin "19") (pinfunction "19_19") (pintype "bidirectional"))
    )
    (net (code "21") (name "AIO_3") (class "Default")
      (node (ref "D8") (pin "C") (pinfunction "2_C") (pintype "passive"))
      (node (ref "J12") (pin "1") (pinfunction "1_1") (pintype "passive"))
      (node (ref "J17") (pin "22") (pinfunction "6_22") (pintype "passive"))
      (node (ref "J17") (pin "6") (pinfunction "6_6") (pintype "passive"))
      (node (ref "J26") (pin "8") (pinfunction "8_8") (pintype "bidirectional"))
      (node (ref "J32") (pin "6") (pinfunction "6_6") (pintype "bidirectional"))
    )
    (net (code "22") (name "AIO_4") (class "Default")
      (node (ref "D9") (pin "C") (pinfunction "2_C") (pintype "passive"))
      (node (ref "J13") (pin "1") (pinfunction "1_1") (pintype "passive"))
      (node (ref "J17") (pin "23") (pinfunction "7_23") (pintype "passive"))
      (node (ref "J17") (pin "7") (pinfunction "7_7") (pintype "passive"))
      (node (ref "J26") (pin "10") (pinfunction "10_10") (pintype "bidirectional"))
      (node (ref "J32") (pin "18") (pinfunction "18_18") (pintype "bidirectional"))
    )
    (net (code "23") (name "AIO_5") (class "Default")
      (node (ref "D10") (pin "C") (pinfunction "2_C") (pintype "passive"))
      (node (ref "J14") (pin "1") (pinfunction "1_1") (pintype "passive"))
      (node (ref "J17") (pin "24") (pinfunction "8_24") (pintype "passive"))
      (node (ref "J17") (pin "8") (pinfunction "8_8") (pintype "passive"))
      (node (ref "J26") (pin "12") (pinfunction "12_12") (pintype "bidirectional"))
      (node (ref "J32") (pin "5") (pinfunction "5_5") (pintype "bidirectional"))
    )
    (net (code "24") (name "AIO_6") (class "Default")
      (node (ref "D11") (pin "C") (pinfunction "2_C") (pintype "passive"))
      (node (ref "J17") (pin "25") (pinfunction "9_25") (pintype "passive"))
      (node (ref "J17") (pin "9") (pinfunction "9_9") (pintype "passive"))
      (node (ref "J20") (pin "1") (pinfunction "1_1") (pintype "passive"))
      (node (ref "J26") (pin "14") (pinfunction "14_14") (pintype "bidirectional"))
      (node (ref "J32") (pin "17") (pinfunction "17_17") (pintype "bidirectional"))
    )
    (net (code "25") (name "AIO_7") (class "Default")
      (node (ref "D12") (pin "C") (pinfunction "2_C") (pintype "passive"))
      (node (ref "J17") (pin "10") (pinfunction "10_10") (pintype "passive"))
      (node (ref "J17") (pin "26") (pinfunction "10_26") (pintype "passive"))
      (node (ref "J21") (pin "1") (pinfunction "1_1") (pintype "passive"))
      (node (ref "J26") (pin "16") (pinfunction "16_16") (pintype "bidirectional"))
      (node (ref "J32") (pin "4") (pinfunction "4_4") (pintype "bidirectional"))
    )
    (net (code "26") (name "AIO_8") (class "Default")
      (node (ref "D13") (pin "C") (pinfunction "2_C") (pintype "passive"))
      (node (ref "J17") (pin "11") (pinfunction "11_11") (pintype "passive"))
      (node (ref "J17") (pin "27") (pinfunction "11_27") (pintype "passive"))
      (node (ref "J22") (pin "1") (pinfunction "1_1") (pintype "passive"))
      (node (ref "J26") (pin "18") (pinfunction "18_18") (pintype "bidirectional"))
      (node (ref "J32") (pin "16") (pinfunction "16_16") (pintype "bidirectional"))
    )
    (net (code "27") (name "AIO_9") (class "Default")
      (node (ref "D14") (pin "C") (pinfunction "2_C") (pintype "passive"))
      (node (ref "J17") (pin "12") (pinfunction "12_12") (pintype "passive"))
      (node (ref "J17") (pin "28") (pinfunction "12_28") (pintype "passive"))
      (node (ref "J23") (pin "1") (pinfunction "1_1") (pintype "passive"))
      (node (ref "J26") (pin "20") (pinfunction "20_20") (pintype "bidirectional"))
      (node (ref "J32") (pin "3") (pinfunction "3_3") (pintype "bidirectional"))
    )
    (net (code "28") (name "AIO_10") (class "Default")
      (node (ref "D15") (pin "C") (pinfunction "2_C") (pintype "passive"))
      (node (ref "J17") (pin "13") (pinfunction "13_13") (pintype "passive"))
      (node (ref "J17") (pin "29") (pinfunction "13_29") (pintype "passive"))
      (node (ref "J24") (pin "1") (pinfunction "1_1") (pintype "passive"))
      (node (ref "J26") (pin "22") (pinfunction "22_22") (pintype "bidirectional"))
      (node (ref "J32") (pin "15") (pinfunction "15_15") (pintype "bidirectional"))
    )
    (net (code "29") (name "AIO_11") (class "Default")
      (node (ref "D16") (pin "C") (pinfunction "2_C") (pintype "passive"))
      (node (ref "J17") (pin "14") (pinfunction "14_14") (pintype "passive"))
      (node (ref "J17") (pin "30") (pinfunction "14_30") (pintype "passive"))
      (node (ref "J25") (pin "1") (pinfunction "1_1") (pintype "passive"))
      (node (ref "J26") (pin "24") (pinfunction "24_24") (pintype "bidirectional"))
      (node (ref "J32") (pin "2") (pinfunction "2_2") (pintype "bidirectional"))
    )
    (net (code "30") (name "BUTTON0") (class "Default")
      (node (ref "S5") (pin "SW1") (pinfunction "P_SW1") (pintype "passive"))
      (node (ref "U50") (pin "16") (pinfunction "P13_16") (pintype "bidirectional"))
    )
    (net (code "31") (name "BUTTON1") (class "Default")
      (node (ref "S7") (pin "SW1") (pinfunction "P_SW1") (pintype "passive"))
      (node (ref "U50") (pin "17") (pinfunction "P14_17") (pintype "bidirectional"))
    )
    (net (code "32") (name "BUTTON2") (class "Default")
      (node (ref "S9") (pin "SW1") (pinfunction "P_SW1") (pintype "passive"))
      (node (ref "U50") (pin "18") (pinfunction "P15_18") (pintype "bidirectional"))
    )
    (net (code "33") (name "BUTTON3") (class "Default")
      (node (ref "S6") (pin "SW1") (pinfunction "P_SW1") (pintype "passive"))
      (node (ref "U50") (pin "11") (pinfunction "P07_11") (pintype "bidirectional"))
    )
    (net (code "34") (name "BUTTON4") (class "Default")
      (node (ref "S8") (pin "SW1") (pinfunction "P_SW1") (pintype "passive"))
      (node (ref "U50") (pin "14") (pinfunction "P11_14") (pintype "bidirectional"))
    )
    (net (code "35") (name "BUTTON5") (class "Default")
      (node (ref "S10") (pin "SW1") (pinfunction "P_SW1") (pintype "passive"))
      (node (ref "U50") (pin "10") (pinfunction "P06_10") (pintype "bidirectional"))
    )
    (net (code "36") (name "DIN0") (class "Default")
      (node (ref "D30") (pin "4") (pinfunction "CH4_4") (pintype "passive"))
      (node (ref "J34") (pin "2") (pinfunction "2_2") (pintype "passive"))
      (node (ref "J35") (pin "11") (pinfunction "2_11") (pintype "passive"))
      (node (ref "J35") (pin "2") (pinfunction "2_2") (pintype "passive"))
      (node (ref "R43") (pin "2") (pinfunction "2_2") (pintype "passive"))
    )
    (net (code "37") (name "DIN0_P") (class "Default")
      (node (ref "D34") (pin "3") (pinfunction "COMM_3") (pintype "passive"))
      (node (ref "R43") (pin "1") (pinfunction "1_1") (pintype "passive"))
      (node (ref "U49") (pin "14") (pinfunction "14_14") (pintype "bidirectional"))
    )
    (net (code "38") (name "DIN1") (class "Default")
      (node (ref "D30") (pin "3") (pinfunction "CH3_3") (pintype "passive"))
      (node (ref "J34") (pin "4") (pinfunction "4_4") (pintype "passive"))
      (node (ref "J35") (pin "12") (pinfunction "3_12") (pintype "passive"))
      (node (ref "J35") (pin "3") (pinfunction "3_3") (pintype "passive"))
      (node (ref "R35") (pin "2") (pinfunction "2_2") (pintype "passive"))
    )
    (net (code "39") (name "DIN1_P") (class "Default")
      (node (ref "D25") (pin "3") (pinfunction "COMM_3") (pintype "passive"))
      (node (ref "R35") (pin "1") (pinfunction "1_1") (pintype "passive"))
      (node (ref "U49") (pin "15") (pinfunction "15_15") (pintype "bidirectional"))
    )
    (net (code "40") (name "DIN2") (class "Default")
      (node (ref "D30") (pin "2") (pinfunction "CH2_2") (pintype "passive"))
      (node (ref "J34") (pin "6") (pinfunction "6_6") (pintype "passive"))
      (node (ref "J35") (pin "13") (pinfunction "4_13") (pintype "passive"))
      (node (ref "J35") (pin "4") (pinfunction "4_4") (pintype "passive"))
      (node (ref "R41") (pin "2") (pinfunction "2_2") (pintype "passive"))
    )
    (net (code "41") (name "DIN2_P") (class "Default")
      (node (ref "D32") (pin "3") (pinfunction "COMM_3") (pintype "passive"))
      (node (ref "R41") (pin "1") (pinfunction "1_1") (pintype "passive"))
      (node (ref "U49") (pin "16") (pinfunction "16/GBIN2_16") (pintype "bidirectional"))
    )
    (net (code "42") (name "DIN3") (class "Default")
      (node (ref "D30") (pin "1") (pinfunction "CH1_1") (pintype "passive"))
      (node (ref "J34") (pin "8") (pinfunction "8_8") (pintype "passive"))
      (node (ref "J35") (pin "14") (pinfunction "5_14") (pintype "passive"))
      (node (ref "J35") (pin "5") (pinfunction "5_5") (pintype "passive"))
      (node (ref "R33") (pin "2") (pinfunction "2_2") (pintype "passive"))
    )
    (net (code "43") (name "DIN3_P") (class "Default")
      (node (ref "D23") (pin "3") (pinfunction "COMM_3") (pintype "passive"))
      (node (ref "R33") (pin "1") (pinfunction "1_1") (pintype "passive"))
      (node (ref "U49") (pin "9") (pinfunction "9/10B_9") (pintype "bidirectional"))
    )
    (net (code "44") (name "DIN4") (class "Default")
      (node (ref "D30") (pin "10") (pinfunction "CH8_10") (pintype "passive"))
      (node (ref "J34") (pin "10") (pinfunction "10_10") (pintype "passive"))
      (node (ref "J35") (pin "15") (pinfunction "6_15") (pintype "passive"))
      (node (ref "J35") (pin "6") (pinfunction "6_6") (pintype "passive"))
      (node (ref "R39") (pin "2") (pinfunction "2_2") (pintype "passive"))
    )
    (net (code "45") (name "DIN4_P") (class "Default")
      (node (ref "D29") (pin "3") (pinfunction "COMM_3") (pintype "passive"))
      (node (ref "R39") (pin "1") (pinfunction "1_1") (pintype "passive"))
      (node (ref "U49") (pin "10") (pinfunction "10/26A_10") (pintype "bidirectional"))
    )
    (net (code "46") (name "DIN5") (class "Default")
      (node (ref "D30") (pin "9") (pinfunction "CH7_9") (pintype "passive"))
      (node (ref "J34") (pin "12") (pinfunction "12_12") (pintype "passive"))
      (node (ref "J35") (pin "16") (pinfunction "7_16") (pintype "passive"))
      (node (ref "J35") (pin "7") (pinfunction "7_7") (pintype "passive"))
      (node (ref "R31") (pin "2") (pinfunction "2_2") (pintype "passive"))
    )
    (net (code "47") (name "DIN5_P") (class "Default")
      (node (ref "D20") (pin "3") (pinfunction "COMM_3") (pintype "passive"))
      (node (ref "R31") (pin "1") (pinfunction "1_1") (pintype "passive"))
      (node (ref "U49") (pin "11") (pinfunction "11_11") (pintype "bidirectional"))
    )
    (net (code "48") (name "DIN6") (class "Default")
      (node (ref "D30") (pin "7") (pinfunction "CH6_7") (pintype "passive"))
      (node (ref "J34") (pin "14") (pinfunction "14_14") (pintype "passive"))
      (node (ref "J35") (pin "17") (pinfunction "8_17") (pintype "passive"))
      (node (ref "J35") (pin "8") (pinfunction "8_8") (pintype "passive"))
      (node (ref "R37") (pin "2") (pinfunction "2_2") (pintype "passive"))
    )
    (net (code "49") (name "DIN6_P") (class "Default")
      (node (ref "D27") (pin "3") (pinfunction "COMM_3") (pintype "passive"))
      (node (ref "R37") (pin "1") (pinfunction "1_1") (pintype "passive"))
      (node (ref "U49") (pin "12") (pinfunction "12_12") (pintype "bidirectional"))
    )
    (net (code "50") (name "DIN7") (class "Default")
      (node (ref "D30") (pin "6") (pinfunction "CH5_6") (pintype "passive"))
      (node (ref "J34") (pin "16") (pinfunction "16_16") (pintype "passive"))
      (node (ref "J35") (pin "18") (pinfunction "9_18") (pintype "passive"))
      (node (ref "J35") (pin "9") (pinfunction "9_9") (pintype "passive"))
      (node (ref "R29") (pin "2") (pinfunction "2_2") (pintype "passive"))
    )
    (net (code "51") (name "DIN7_P") (class "Default")
      (node (ref "D18") (pin "3") (pinfunction "COMM_3") (pintype "passive"))
      (node (ref "R29") (pin "1") (pinfunction "1_1") (pintype "passive"))
      (node (ref "U49") (pin "13") (pinfunction "13/26B_13") (pintype "bidirectional"))
    )
    (net (code "52") (name "DOUT0") (class "Default")
      (node (ref "D21") (pin "10") (pinfunction "CH8_10") (pintype "passive"))
      (node (ref "J31") (pin "2") (pinfunction "2_2") (pintype "passive"))
      (node (ref "J33") (pin "11") (pinfunction "2_11") (pintype "passive"))
      (node (ref "J33") (pin "2") (pinfunction "2_2") (pintype "passive"))
      (node (ref "R28") (pin "2") (pinfunction "2_2") (pintype "passive"))
    )
    (net (code "53") (name "DOUT0_P") (class "Default")
      (node (ref "D17") (pin "3") (pinfunction "COMM_3") (pintype "passive"))
      (node (ref "R28") (pin "1") (pinfunction "1_1") (pintype "passive"))
      (node (ref "U49") (pin "8") (pinfunction "8_8") (pintype "bidirectional"))
    )
    (net (code "54") (name "DOUT1") (class "Default")
      (node (ref "D21") (pin "9") (pinfunction "CH7_9") (pintype "passive"))
      (node (ref "J31") (pin "4") (pinfunction "4_4") (pintype "passive"))
      (node (ref "J33") (pin "12") (pinfunction "3_12") (pintype "passive"))
      (node (ref "J33") (pin "3") (pinfunction "3_3") (pintype "passive"))
      (node (ref "R30") (pin "2") (pinfunction "2_2") (pintype "passive"))
    )
    (net (code "55") (name "DOUT1_P") (class "Default")
      (node (ref "D19") (pin "3") (pinfunction "COMM_3") (pintype "passive"))
      (node (ref "R30") (pin "1") (pinfunction "1_1") (pintype "passive"))
      (node (ref "U49") (pin "7") (pinfunction "7/10A_7") (pintype "bidirectional"))
    )
    (net (code "56") (name "DOUT2") (class "Default")
      (node (ref "D21") (pin "7") (pinfunction "CH6_7") (pintype "passive"))
      (node (ref "J31") (pin "6") (pinfunction "6_6") (pintype "passive"))
      (node (ref "J33") (pin "13") (pinfunction "4_13") (pintype "passive"))
      (node (ref "J33") (pin "4") (pinfunction "4_4") (pintype "passive"))
      (node (ref "R32") (pin "2") (pinfunction "2_2") (pintype "passive"))
    )
    (net (code "57") (name "DOUT2_P") (class "Default")
      (node (ref "D22") (pin "3") (pinfunction "COMM_3") (pintype "passive"))
      (node (ref "R32") (pin "1") (pinfunction "1_1") (pintype "passive"))
      (node (ref "U49") (pin "6") (pinfunction "6_6") (pintype "bidirectional"))
    )
    (net (code "58") (name "DOUT3") (class "Default")
      (node (ref "D21") (pin "6") (pinfunction "CH5_6") (pintype "passive"))
      (node (ref "J31") (pin "8") (pinfunction "8_8") (pintype "passive"))
      (node (ref "J33") (pin "14") (pinfunction "5_14") (pintype "passive"))
      (node (ref "J33") (pin "5") (pinfunction "5_5") (pintype "passive"))
      (node (ref "R34") (pin "2") (pinfunction "2_2") (pintype "passive"))
    )
    (net (code "59") (name "DOUT3_P") (class "Default")
      (node (ref "D24") (pin "3") (pinfunction "COMM_3") (pintype "passive"))
      (node (ref "R34") (pin "1") (pinfunction "1_1") (pintype "passive"))
      (node (ref "U49") (pin "5") (pinfunction "5/3B_5") (pintype "bidirectional"))
    )
    (net (code "60") (name "DOUT4") (class "Default")
      (node (ref "D21") (pin "1") (pinfunction "CH1_1") (pintype "passive"))
      (node (ref "J31") (pin "10") (pinfunction "10_10") (pintype "passive"))
      (node (ref "J33") (pin "15") (pinfunction "6_15") (pintype "passive"))
      (node (ref "J33") (pin "6") (pinfunction "6_6") (pintype "passive"))
      (node (ref "R36") (pin "2") (pinfunction "2_2") (pintype "passive"))
    )
    (net (code "61") (name "DOUT4_P") (class "Default")
      (node (ref "D26") (pin "3") (pinfunction "COMM_3") (pintype "passive"))
      (node (ref "R36") (pin "1") (pinfunction "1_1") (pintype "passive"))
      (node (ref "U49") (pin "4") (pinfunction "4_4") (pintype "bidirectional"))
    )
    (net (code "62") (name "DOUT5") (class "Default")
      (node (ref "D21") (pin "2") (pinfunction "CH2_2") (pintype "passive"))
      (node (ref "J31") (pin "12") (pinfunction "12_12") (pintype "passive"))
      (node (ref "J33") (pin "16") (pinfunction "7_16") (pintype "passive"))
      (node (ref "J33") (pin "7") (pinfunction "7_7") (pintype "passive"))
      (node (ref "R38") (pin "2") (pinfunction "2_2") (pintype "passive"))
    )
    (net (code "63") (name "DOUT5_P") (class "Default")
      (node (ref "D28") (pin "3") (pinfunction "COMM_3") (pintype "passive"))
      (node (ref "R38") (pin "1") (pinfunction "1_1") (pintype "passive"))
      (node (ref "U49") (pin "3") (pinfunction "3/3A_3") (pintype "bidirectional"))
    )
    (net (code "64") (name "DOUT6") (class "Default")
      (node (ref "D21") (pin "3") (pinfunction "CH3_3") (pintype "passive"))
      (node (ref "J31") (pin "14") (pinfunction "14_14") (pintype "passive"))
      (node (ref "J33") (pin "17") (pinfunction "8_17") (pintype "passive"))
      (node (ref "J33") (pin "8") (pinfunction "8_8") (pintype "passive"))
      (node (ref "R40") (pin "2") (pinfunction "2_2") (pintype "passive"))
    )
    (net (code "65") (name "DOUT6_P") (class "Default")
      (node (ref "D31") (pin "3") (pinfunction "COMM_3") (pintype "passive"))
      (node (ref "R40") (pin "1") (pinfunction "1_1") (pintype "passive"))
      (node (ref "U49") (pin "2") (pinfunction "2_2") (pintype "bidirectional"))
    )
    (net (code "66") (name "DOUT7") (class "Default")
      (node (ref "D21") (pin "4") (pinfunction "CH4_4") (pintype "passive"))
      (node (ref "J31") (pin "16") (pinfunction "16_16") (pintype "passive"))
      (node (ref "J33") (pin "18") (pinfunction "9_18") (pintype "passive"))
      (node (ref "J33") (pin "9") (pinfunction "9_9") (pintype "passive"))
      (node (ref "R42") (pin "2") (pinfunction "2_2") (pintype "passive"))
    )
    (net (code "67") (name "DOUT7_P") (class "Default")
      (node (ref "D33") (pin "3") (pinfunction "COMM_3") (pintype "passive"))
      (node (ref "R42") (pin "1") (pinfunction "1_1") (pintype "passive"))
      (node (ref "U49") (pin "1") (pinfunction "1_1") (pintype "bidirectional"))
    )
    (net (code "68") (name "GND") (class "Default")
      (node (ref "C1") (pin "2") (pinfunction "2_2") (pintype "passive"))
      (node (ref "C10") (pin "1") (pinfunction "1_1") (pintype "passive"))
      (node (ref "C11") (pin "1") (pinfunction "1_1") (pintype "passive"))
      (node (ref "C12") (pin "1") (pinfunction "1_1") (pintype "passive"))
      (node (ref "C13") (pin "1") (pinfunction "1_1") (pintype "passive"))
      (node (ref "C14") (pin "1") (pinfunction "1_1") (pintype "passive"))
      (node (ref "C15") (pin "1") (pinfunction "1_1") (pintype "passive"))
      (node (ref "C16") (pin "1") (pinfunction "1_1") (pintype "passive"))
      (node (ref "C17") (pin "1") (pinfunction "1_1") (pintype "passive"))
      (node (ref "C18") (pin "1") (pinfunction "1_1") (pintype "passive"))
      (node (ref "C19") (pin "1") (pinfunction "1_1") (pintype "passive"))
      (node (ref "C2") (pin "2") (pinfunction "2_2") (pintype "passive"))
      (node (ref "C20") (pin "1") (pinfunction "1_1") (pintype "passive"))
      (node (ref "C21") (pin "1") (pinfunction "1_1") (pintype "passive"))
      (node (ref "C22") (pin "1") (pinfunction "1_1") (pintype "passive"))
      (node (ref "C23") (pin "1") (pinfunction "1_1") (pintype "passive"))
      (node (ref "C24") (pin "1") (pinfunction "1_1") (pintype "passive"))
      (node (ref "C25") (pin "1") (pinfunction "1_1") (pintype "passive"))
      (node (ref "C26") (pin "1") (pinfunction "1_1") (pintype "passive"))
      (node (ref "C27") (pin "1") (pinfunction "1_1") (pintype "passive"))
      (node (ref "C28") (pin "1") (pinfunction "1_1") (pintype "passive"))
      (node (ref "C29") (pin "1") (pinfunction "1_1") (pintype "passive"))
      (node (ref "C3") (pin "1") (pinfunction "1_1") (pintype "passive"))
      (node (ref "C30") (pin "1") (pinfunction "1_1") (pintype "passive"))
      (node (ref "C31") (pin "1") (pinfunction "1_1") (pintype "passive"))
      (node (ref "C36") (pin "1") (pinfunction "1_1") (pintype "passive"))
      (node (ref "C37") (pin "1") (pinfunction "1_1") (pintype "passive"))
      (node (ref "C38") (pin "1") (pinfunction "1_1") (pintype "passive"))
      (node (ref "C39") (pin "1") (pinfunction "1_1") (pintype "passive"))
      (node (ref "C4") (pin "1") (pinfunction "1_1") (pintype "passive"))
      (node (ref "C40") (pin "1") (pinfunction "1_1") (pintype "passive"))
      (node (ref "C42") (pin "1") (pinfunction "1_1") (pintype "passive"))
      (node (ref "C43") (pin "1") (pinfunction "1_1") (pintype "passive"))
      (node (ref "C44") (pin "2") (pinfunction "2_2") (pintype "passive"))
      (node (ref "C45") (pin "2") (pinfunction "2_2") (pintype "passive"))
      (node (ref "C46") (pin "2") (pinfunction "2_2") (pintype "passive"))
      (node (ref "C47") (pin "2") (pinfunction "2_2") (pintype "passive"))
      (node (ref "C48") (pin "2") (pinfunction "2_2") (pintype "passive"))
      (node (ref "C49") (pin "2") (pinfunction "2_2") (pintype "passive"))
      (node (ref "C5") (pin "1") (pinfunction "1_1") (pintype "passive"))
      (node (ref "C6") (pin "1") (pinfunction "1_1") (pintype "passive"))
      (node (ref "C7") (pin "1") (pinfunction "1_1") (pintype "passive"))
      (node (ref "C8") (pin "1") (pinfunction "1_1") (pintype "passive"))
      (node (ref "C9") (pin "1") (pinfunction "1_1") (pintype "passive"))
      (node (ref "D17") (pin "1") (pinfunction "A_1") (pintype "passive"))
      (node (ref "D18") (pin "1") (pinfunction "A_1") (pintype "passive"))
      (node (ref "D19") (pin "1") (pinfunction "A_1") (pintype "passive"))
      (node (ref "D20") (pin "1") (pinfunction "A_1") (pintype "passive"))
      (node (ref "D21") (pin "5") (pinfunction "VSS_5") (pintype "power_in"))
      (node (ref "D22") (pin "1") (pinfunction "A_1") (pintype "passive"))
      (node (ref "D23") (pin "1") (pinfunction "A_1") (pintype "passive"))
      (node (ref "D24") (pin "1") (pinfunction "A_1") (pintype "passive"))
      (node (ref "D25") (pin "1") (pinfunction "A_1") (pintype "passive"))
      (node (ref "D26") (pin "1") (pinfunction "A_1") (pintype "passive"))
      (node (ref "D27") (pin "1") (pinfunction "A_1") (pintype "passive"))
      (node (ref "D28") (pin "1") (pinfunction "A_1") (pintype "passive"))
      (node (ref "D29") (pin "1") (pinfunction "A_1") (pintype "passive"))
      (node (ref "D30") (pin "5") (pinfunction "VSS_5") (pintype "power_in"))
      (node (ref "D31") (pin "1") (pinfunction "A_1") (pintype "passive"))
      (node (ref "D32") (pin "1") (pinfunction "A_1") (pintype "passive"))
      (node (ref "D33") (pin "1") (pinfunction "A_1") (pintype "passive"))
      (node (ref "D34") (pin "1") (pinfunction "A_1") (pintype "passive"))
      (node (ref "J1") (pin "GND$1") (pinfunction "2_GND$1") (pintype "passive"))
      (node (ref "J1") (pin "GND$2") (pinfunction "2_GND$2") (pintype "passive"))
      (node (ref "J1") (pin "GND$3") (pinfunction "2_GND$3") (pintype "passive"))
      (node (ref "J1") (pin "GND$4") (pinfunction "2_GND$4") (pintype "passive"))
      (node (ref "J15") (pin "GND@1") (pinfunction "2_GND@1") (pintype "passive"))
      (node (ref "J15") (pin "GND@2") (pinfunction "2_GND@2") (pintype "passive"))
      (node (ref "J15") (pin "GND@3") (pinfunction "2_GND@3") (pintype "passive"))
      (node (ref "J15") (pin "GND@4") (pinfunction "2_GND@4") (pintype "passive"))
      (node (ref "J16") (pin "GND$1") (pinfunction "2_GND$1") (pintype "passive"))
      (node (ref "J16") (pin "GND$2") (pinfunction "2_GND$2") (pintype "passive"))
      (node (ref "J16") (pin "GND$3") (pinfunction "2_GND$3") (pintype "passive"))
      (node (ref "J16") (pin "GND$4") (pinfunction "2_GND$4") (pintype "passive"))
      (node (ref "J18") (pin "GND@1") (pinfunction "2_GND@1") (pintype "passive"))
      (node (ref "J18") (pin "GND@2") (pinfunction "2_GND@2") (pintype "passive"))
      (node (ref "J18") (pin "GND@3") (pinfunction "2_GND@3") (pintype "passive"))
      (node (ref "J18") (pin "GND@4") (pinfunction "2_GND@4") (pintype "passive"))
      (node (ref "J19") (pin "GND$1") (pinfunction "2_GND$1") (pintype "passive"))
      (node (ref "J19") (pin "GND$2") (pinfunction "2_GND$2") (pintype "passive"))
      (node (ref "J19") (pin "GND$3") (pinfunction "2_GND$3") (pintype "passive"))
      (node (ref "J19") (pin "GND$4") (pinfunction "2_GND$4") (pintype "passive"))
      (node (ref "J2") (pin "GND$1") (pinfunction "2_GND$1") (pintype "passive"))
      (node (ref "J2") (pin "GND$2") (pinfunction "2_GND$2") (pintype "passive"))
      (node (ref "J2") (pin "GND$3") (pinfunction "2_GND$3") (pintype "passive"))
      (node (ref "J2") (pin "GND$4") (pinfunction "2_GND$4") (pintype "passive"))
      (node (ref "J27") (pin "GND@1") (pinfunction "2_GND@1") (pintype "passive"))
      (node (ref "J27") (pin "GND@2") (pinfunction "2_GND@2") (pintype "passive"))
      (node (ref "J27") (pin "GND@3") (pinfunction "2_GND@3") (pintype "passive"))
      (node (ref "J27") (pin "GND@4") (pinfunction "2_GND@4") (pintype "passive"))
      (node (ref "J28") (pin "GND$1") (pinfunction "2_GND$1") (pintype "passive"))
      (node (ref "J28") (pin "GND$2") (pinfunction "2_GND$2") (pintype "passive"))
      (node (ref "J28") (pin "GND$3") (pinfunction "2_GND$3") (pintype "passive"))
      (node (ref "J28") (pin "GND$4") (pinfunction "2_GND$4") (pintype "passive"))
      (node (ref "J3") (pin "GND$1") (pinfunction "2_GND$1") (pintype "passive"))
      (node (ref "J3") (pin "GND$2") (pinfunction "2_GND$2") (pintype "passive"))
      (node (ref "J3") (pin "GND$3") (pinfunction "2_GND$3") (pintype "passive"))
      (node (ref "J3") (pin "GND$4") (pinfunction "2_GND$4") (pintype "passive"))
      (node (ref "J30") (pin "2") (pinfunction "2_2") (pintype "passive"))
      (node (ref "J31") (pin "1") (pinfunction "1_1") (pintype "passive"))
      (node (ref "J31") (pin "11") (pinfunction "11_11") (pintype "passive"))
      (node (ref "J31") (pin "13") (pinfunction "13_13") (pintype "passive"))
      (node (ref "J31") (pin "15") (pinfunction "15_15") (pintype "passive"))
      (node (ref "J31") (pin "3") (pinfunction "3_3") (pintype "passive"))
      (node (ref "J31") (pin "5") (pinfunction "5_5") (pintype "passive"))
      (node (ref "J31") (pin "7") (pinfunction "7_7") (pintype "passive"))
      (node (ref "J31") (pin "9") (pinfunction "9_9") (pintype "passive"))
      (node (ref "J32") (pin "PAD1") (pinfunction "PAD1_PAD1") (pintype "bidirectional"))
      (node (ref "J32") (pin "PAD2") (pinfunction "PAD2_PAD2") (pintype "bidirectional"))
      (node (ref "J33") (pin "1") (pinfunction "1_1") (pintype "passive"))
      (node (ref "J33") (pin "10") (pinfunction "1_10") (pintype "passive"))
      (node (ref "J34") (pin "1") (pinfunction "1_1") (pintype "passive"))
      (node (ref "J34") (pin "11") (pinfunction "11_11") (pintype "passive"))
      (node (ref "J34") (pin "13") (pinfunction "13_13") (pintype "passive"))
      (node (ref "J34") (pin "15") (pinfunction "15_15") (pintype "passive"))
      (node (ref "J34") (pin "3") (pinfunction "3_3") (pintype "passive"))
      (node (ref "J34") (pin "5") (pinfunction "5_5") (pintype "passive"))
      (node (ref "J34") (pin "7") (pinfunction "7_7") (pintype "passive"))
      (node (ref "J34") (pin "9") (pinfunction "9_9") (pintype "passive"))
      (node (ref "J35") (pin "1") (pinfunction "1_1") (pintype "passive"))
      (node (ref "J35") (pin "10") (pinfunction "1_10") (pintype "passive"))
      (node (ref "J4") (pin "GND$1") (pinfunction "2_GND$1") (pintype "passive"))
      (node (ref "J4") (pin "GND$2") (pinfunction "2_GND$2") (pintype "passive"))
      (node (ref "J4") (pin "GND$3") (pinfunction "2_GND$3") (pintype "passive"))
      (node (ref "J4") (pin "GND$4") (pinfunction "2_GND$4") (pintype "passive"))
      (node (ref "J5") (pin "GND@1") (pinfunction "2_GND@1") (pintype "passive"))
      (node (ref "J5") (pin "GND@2") (pinfunction "2_GND@2") (pintype "passive"))
      (node (ref "J5") (pin "GND@3") (pinfunction "2_GND@3") (pintype "passive"))
      (node (ref "J5") (pin "GND@4") (pinfunction "2_GND@4") (pintype "passive"))
      (node (ref "J6") (pin "GND@1") (pinfunction "2_GND@1") (pintype "passive"))
      (node (ref "J6") (pin "GND@2") (pinfunction "2_GND@2") (pintype "passive"))
      (node (ref "J6") (pin "GND@3") (pinfunction "2_GND@3") (pintype "passive"))
      (node (ref "J6") (pin "GND@4") (pinfunction "2_GND@4") (pintype "passive"))
      (node (ref "J7") (pin "GND@1") (pinfunction "2_GND@1") (pintype "passive"))
      (node (ref "J7") (pin "GND@2") (pinfunction "2_GND@2") (pintype "passive"))
      (node (ref "J7") (pin "GND@3") (pinfunction "2_GND@3") (pintype "passive"))
      (node (ref "J7") (pin "GND@4") (pinfunction "2_GND@4") (pintype "passive"))
      (node (ref "J8") (pin "GND@1") (pinfunction "2_GND@1") (pintype "passive"))
      (node (ref "J8") (pin "GND@2") (pinfunction "2_GND@2") (pintype "passive"))
      (node (ref "J8") (pin "GND@3") (pinfunction "2_GND@3") (pintype "passive"))
      (node (ref "J8") (pin "GND@4") (pinfunction "2_GND@4") (pintype "passive"))
      (node (ref "Q5") (pin "2") (pinfunction "S_2") (pintype "bidirectional"))
      (node (ref "Q6") (pin "2") (pinfunction "S_2") (pintype "bidirectional"))
      (node (ref "Q7") (pin "2") (pinfunction "S_2") (pintype "bidirectional"))
      (node (ref "Q8") (pin "2") (pinfunction "S_2") (pintype "bidirectional"))
      (node (ref "R10") (pin "2") (pinfunction "2_2") (pintype "passive"))
      (node (ref "R11") (pin "1") (pinfunction "1_1") (pintype "passive"))
      (node (ref "R12") (pin "1") (pinfunction "1_1") (pintype "passive"))
      (node (ref "R13") (pin "1") (pinfunction "1_1") (pintype "passive"))
      (node (ref "R14") (pin "1") (pinfunction "1_1") (pintype "passive"))
      (node (ref "R15") (pin "1") (pinfunction "1_1") (pintype "passive"))
      (node (ref "R16") (pin "1") (pinfunction "1_1") (pintype "passive"))
      (node (ref "R17") (pin "1") (pinfunction "1_1") (pintype "passive"))
      (node (ref "R18") (pin "1") (pinfunction "1_1") (pintype "passive"))
      (node (ref "R19") (pin "2") (pinfunction "2_2") (pintype "passive"))
      (node (ref "R20") (pin "2") (pinfunction "2_2") (pintype "passive"))
      (node (ref "R21") (pin "2") (pinfunction "2_2") (pintype "passive"))
      (node (ref "R7") (pin "2") (pinfunction "2_2") (pintype "passive"))
      (node (ref "R8") (pin "2") (pinfunction "2_2") (pintype "passive"))
      (node (ref "R9") (pin "2") (pinfunction "2_2") (pintype "passive"))
      (node (ref "S1") (pin "2") (pinfunction "1_2") (pintype "passive"))
      (node (ref "S10") (pin "SW2") (pinfunction "S_SW2") (pintype "passive"))
      (node (ref "S2") (pin "2") (pinfunction "1_2") (pintype "passive"))
      (node (ref "S3") (pin "2") (pinfunction "1_2") (pintype "passive"))
      (node (ref "S4") (pin "2") (pinfunction "1_2") (pintype "passive"))
      (node (ref "S5") (pin "SW2") (pinfunction "S_SW2") (pintype "passive"))
      (node (ref "S6") (pin "SW2") (pinfunction "S_SW2") (pintype "passive"))
      (node (ref "S7") (pin "SW2") (pinfunction "S_SW2") (pintype "passive"))
      (node (ref "S8") (pin "SW2") (pinfunction "S_SW2") (pintype "passive"))
      (node (ref "S9") (pin "SW2") (pinfunction "S_SW2") (pintype "passive"))
      (node (ref "TP3") (pin "1") (pinfunction "TP_1") (pintype "bidirectional"))
      (node (ref "TP4") (pin "1") (pinfunction "TP_1") (pintype "bidirectional"))
      (node (ref "TP5") (pin "1") (pinfunction "TP_1") (pintype "bidirectional"))
      (node (ref "U1") (pin "4") (pinfunction "GND_4") (pintype "power_in"))
      (node (ref "U10") (pin "2") (pinfunction "GND_2") (pintype "power_in"))
      (node (ref "U11") (pin "4") (pinfunction "GND_4") (pintype "power_in"))
      (node (ref "U12") (pin "4") (pinfunction "GND_4") (pintype "power_in"))
      (node (ref "U13") (pin "4") (pinfunction "GND_4") (pintype "power_in"))
      (node (ref "U14") (pin "4") (pinfunction "GND_4") (pintype "power_in"))
      (node (ref "U15") (pin "4") (pinfunction "GND_4") (pintype "power_in"))
      (node (ref "U16") (pin "4") (pinfunction "GND_4") (pintype "power_in"))
      (node (ref "U17") (pin "4") (pinfunction "GND_4") (pintype "power_in"))
      (node (ref "U18") (pin "4") (pinfunction "GND_4") (pintype "power_in"))
      (node (ref "U19") (pin "4") (pinfunction "GND_4") (pintype "power_in"))
      (node (ref "U2") (pin "4") (pinfunction "GND_4") (pintype "power_in"))
      (node (ref "U20") (pin "4") (pinfunction "GND_4") (pintype "power_in"))
      (node (ref "U21") (pin "4") (pinfunction "GND_4") (pintype "power_in"))
      (node (ref "U22") (pin "4") (pinfunction "GND_4") (pintype "power_in"))
      (node (ref "U23") (pin "4") (pinfunction "GND_4") (pintype "power_in"))
      (node (ref "U24") (pin "4") (pinfunction "GND_4") (pintype "power_in"))
      (node (ref "U25") (pin "4") (pinfunction "GND_4") (pintype "power_in"))
      (node (ref "U26") (pin "4") (pinfunction "GND_4") (pintype "power_in"))
      (node (ref "U27") (pin "4") (pinfunction "GND_4") (pintype "power_in"))
      (node (ref "U28") (pin "4") (pinfunction "GND_4") (pintype "power_in"))
      (node (ref "U29") (pin "4") (pinfunction "GND_4") (pintype "power_in"))
      (node (ref "U3") (pin "4") (pinfunction "GND_4") (pintype "power_in"))
      (node (ref "U30") (pin "4") (pinfunction "GND_4") (pintype "power_in"))
      (node (ref "U31") (pin "4") (pinfunction "GND_4") (pintype "power_in"))
      (node (ref "U32") (pin "4") (pinfunction "GND_4") (pintype "power_in"))
      (node (ref "U33") (pin "4") (pinfunction "GND_4") (pintype "power_in"))
      (node (ref "U34") (pin "4") (pinfunction "GND_4") (pintype "power_in"))
      (node (ref "U35") (pin "4") (pinfunction "GND_4") (pintype "power_in"))
      (node (ref "U36") (pin "4") (pinfunction "GND_4") (pintype "power_in"))
      (node (ref "U37") (pin "4") (pinfunction "GND_4") (pintype "power_in"))
      (node (ref "U38") (pin "4") (pinfunction "GND_4") (pintype "power_in"))
      (node (ref "U39") (pin "4") (pinfunction "GND_4") (pintype "power_in"))
      (node (ref "U4") (pin "4") (pinfunction "GND_4") (pintype "power_in"))
      (node (ref "U40") (pin "4") (pinfunction "GND_4") (pintype "power_in"))
      (node (ref "U41") (pin "4") (pinfunction "GND_4") (pintype "power_in"))
      (node (ref "U42") (pin "4") (pinfunction "GND_4") (pintype "power_in"))
      (node (ref "U43") (pin "CASE1") (pinfunction "CASE_CASE1") (pintype "bidirectional"))
      (node (ref "U43") (pin "CASE2") (pinfunction "CASE_CASE2") (pintype "bidirectional"))
      (node (ref "U44") (pin "CASE1") (pinfunction "CASE_CASE1") (pintype "bidirectional"))
      (node (ref "U44") (pin "CASE2") (pinfunction "CASE_CASE2") (pintype "bidirectional"))
      (node (ref "U45") (pin "CASE1") (pinfunction "CASE_CASE1") (pintype "bidirectional"))
      (node (ref "U45") (pin "CASE2") (pinfunction "CASE_CASE2") (pintype "bidirectional"))
      (node (ref "U46") (pin "CASE1") (pinfunction "CASE_CASE1") (pintype "bidirectional"))
      (node (ref "U46") (pin "CASE2") (pinfunction "CASE_CASE2") (pintype "bidirectional"))
      (node (ref "U47") (pin "B5") (pinfunction "GND_B5") (pintype "power_in"))
      (node (ref "U47") (pin "C1") (pinfunction "GND_C1") (pintype "power_in"))
      (node (ref "U47") (pin "C2") (pinfunction "GND_C2") (pintype "power_in"))
      (node (ref "U47") (pin "C5") (pinfunction "SYNC/MODE_C5") (pintype "input"))
      (node (ref "U47") (pin "D5") (pinfunction "GND_D5") (pintype "power_in"))
      (node (ref "U48") (pin "4") (pinfunction "AGND_4") (pintype "bidirectional"))
      (node (ref "U49") (pin "GND@1") (pinfunction "GND_GND@1") (pintype "power_in"))
      (node (ref "U49") (pin "GND@2") (pinfunction "GND_GND@2") (pintype "power_in"))
      (node (ref "U5") (pin "4") (pinfunction "GND_4") (pintype "power_in"))
      (node (ref "U50") (pin "12") (pinfunction "GND_12") (pintype "bidirectional"))
      (node (ref "U50") (pin "2") (pinfunction "A1_2") (pintype "bidirectional"))
      (node (ref "U50") (pin "21") (pinfunction "A0_21") (pintype "bidirectional"))
      (node (ref "U50") (pin "3") (pinfunction "A2_3") (pintype "bidirectional"))
      (node (ref "U51") (pin "10") (pinfunction "C+_10") (pintype "input"))
      (node (ref "U51") (pin "12") (pinfunction "~{EN}_12") (pintype "input"))
      (node (ref "U51") (pin "14") (pinfunction "D+_14") (pintype "input"))
      (node (ref "U51") (pin "15") (pinfunction "D-_15") (pintype "input"))
      (node (ref "U51") (pin "8") (pinfunction "GND_8") (pintype "power_in"))
      (node (ref "U51") (pin "9") (pinfunction "C-_9") (pintype "input"))
      (node (ref "U52") (pin "4") (pinfunction "GND_4") (pintype "power_in"))
      (node (ref "U52") (pin "PAD") (pinfunction "GND_PAD") (pintype "power_in"))
      (node (ref "U53") (pin "3") (pinfunction "BIN_3") (pintype "input"))
      (node (ref "U53") (pin "4") (pinfunction "GND_4") (pintype "power_in"))
      (node (ref "U53") (pin "PAD") (pinfunction "GND_PAD") (pintype "power_in"))
      (node (ref "U6") (pin "4") (pinfunction "GND_4") (pintype "power_in"))
      (node (ref "U7") (pin "4") (pinfunction "GND_4") (pintype "power_in"))
      (node (ref "U8") (pin "4") (pinfunction "GND_4") (pintype "power_in"))
      (node (ref "U9") (pin "4") (pinfunction "GND_4") (pintype "power_in"))
    )
    (net (code "69") (name "HARP_CLKOUT") (class "Default")
      (node (ref "U48") (pin "2") (pinfunction "A1_2") (pintype "bidirectional"))
      (node (ref "U49") (pin "24") (pinfunction "24_24") (pintype "bidirectional"))
    )
    (net (code "70") (name "I2C_SCL") (class "Default")
      (node (ref "R23") (pin "2") (pinfunction "2_2") (pintype "passive"))
      (node (ref "U49") (pin "23") (pinfunction "23_23") (pintype "bidirectional"))
      (node (ref "U50") (pin "22") (pinfunction "SCL_22") (pintype "bidirectional"))
    )
    (net (code "71") (name "I2C_SDA") (class "Default")
      (node (ref "R24") (pin "2") (pinfunction "2_2") (pintype "passive"))
      (node (ref "U49") (pin "22") (pinfunction "22_22") (pintype "bidirectional"))
      (node (ref "U50") (pin "23") (pinfunction "SDA_23") (pintype "bidirectional"))
    )
    (net (code "72") (name "LVDS_IN_0") (class "Default")
      (node (ref "U49") (pin "18") (pinfunction "18_18") (pintype "bidirectional"))
      (node (ref "U51") (pin "3") (pinfunction "AOUT_3") (pintype "output"))
    )
    (net (code "73") (name "LVDS_IN_1") (class "Default")
      (node (ref "U49") (pin "17") (pinfunction "17_17") (pintype "bidirectional"))
      (node (ref "U51") (pin "5") (pinfunction "BOUT_5") (pintype "output"))
    )
    (net (code "74") (name "LVDS_OUT_0") (class "Default")
      (node (ref "U49") (pin "19") (pinfunction "19_19") (pintype "bidirectional"))
      (node (ref "U52") (pin "3") (pinfunction "BIN_3") (pintype "input"))
    )
    (net (code "75") (name "LVDS_OUT_1") (class "Default")
      (node (ref "U49") (pin "20") (pinfunction "20_20") (pintype "bidirectional"))
      (node (ref "U52") (pin "2") (pinfunction "AIN_2") (pintype "input"))
    )
    (net (code "76") (name "LVDS_OUT_2") (class "Default")
      (node (ref "U49") (pin "21") (pinfunction "21_21") (pintype "bidirectional"))
      (node (ref "U53") (pin "2") (pinfunction "AIN_2") (pintype "input"))
    )
    (net (code "77") (name "NEOPIXEL_DIN") (class "Default")
      (node (ref "J30") (pin "1") (pinfunction "1_1") (pintype "passive"))
      (node (ref "U10") (pin "3") (pinfunction "A_3") (pintype "bidirectional"))
    )
    (net (code "78") (name "Net-(C32-Pad1)") (class "Default")
      (node (ref "C32") (pin "1") (pinfunction "1_1") (pintype "passive"))
      (node (ref "R7") (pin "1") (pinfunction "1_1") (pintype "passive"))
    )
    (net (code "79") (name "Net-(C33-Pad1)") (class "Default")
      (node (ref "C33") (pin "1") (pinfunction "1_1") (pintype "passive"))
      (node (ref "R8") (pin "1") (pinfunction "1_1") (pintype "passive"))
    )
    (net (code "80") (name "Net-(C34-Pad1)") (class "Default")
      (node (ref "C34") (pin "1") (pinfunction "1_1") (pintype "passive"))
      (node (ref "R9") (pin "1") (pinfunction "1_1") (pintype "passive"))
    )
    (net (code "81") (name "Net-(C35-Pad1)") (class "Default")
      (node (ref "C35") (pin "1") (pinfunction "1_1") (pintype "passive"))
      (node (ref "R10") (pin "1") (pinfunction "1_1") (pintype "passive"))
    )
    (net (code "82") (name "Net-(J1-1)") (class "Default")
      (node (ref "J1") (pin "CLK") (pinfunction "1_CLK") (pintype "passive"))
      (node (ref "U43") (pin "1X6") (pinfunction "COM_A_1X6") (pintype "bidirectional"))
    )
    (net (code "83") (name "Net-(J2-1)") (class "Default")
      (node (ref "J2") (pin "CLK") (pinfunction "1_CLK") (pintype "passive"))
      (node (ref "U44") (pin "1X6") (pinfunction "COM_A_1X6") (pintype "bidirectional"))
    )
    (net (code "84") (name "Net-(J3-1)") (class "Default")
      (node (ref "J3") (pin "CLK") (pinfunction "1_CLK") (pintype "passive"))
      (node (ref "U45") (pin "1X6") (pinfunction "COM_A_1X6") (pintype "bidirectional"))
    )
    (net (code "85") (name "Net-(J4-1)") (class "Default")
      (node (ref "J4") (pin "CLK") (pinfunction "1_CLK") (pintype "passive"))
      (node (ref "U46") (pin "1X6") (pinfunction "COM_A_1X6") (pintype "bidirectional"))
    )
    (net (code "86") (name "Net-(J5-1)") (class "Default")
      (node (ref "J5") (pin "SIG") (pinfunction "1_SIG") (pintype "passive"))
      (node (ref "U43") (pin "5") (pinfunction "NO_A_5") (pintype "bidirectional"))
    )
    (net (code "87") (name "Net-(J6-1)") (class "Default")
      (node (ref "J6") (pin "SIG") (pinfunction "1_SIG") (pintype "passive"))
      (node (ref "U44") (pin "5") (pinfunction "NO_A_5") (pintype "bidirectional"))
    )
    (net (code "88") (name "Net-(J7-1)") (class "Default")
      (node (ref "J7") (pin "SIG") (pinfunction "1_SIG") (pintype "passive"))
      (node (ref "U45") (pin "5") (pinfunction "NO_A_5") (pintype "bidirectional"))
    )
    (net (code "89") (name "Net-(J8-1)") (class "Default")
      (node (ref "J8") (pin "SIG") (pinfunction "1_SIG") (pintype "passive"))
      (node (ref "U46") (pin "5") (pinfunction "NO_A_5") (pintype "bidirectional"))
    )
    (net (code "90") (name "Net-(J15-1)") (class "Default")
      (node (ref "J15") (pin "SIG") (pinfunction "1_SIG") (pintype "passive"))
      (node (ref "J16") (pin "CLK") (pinfunction "1_CLK") (pintype "passive"))
    )
    (net (code "91") (name "Net-(J18-1)") (class "Default")
      (node (ref "J18") (pin "SIG") (pinfunction "1_SIG") (pintype "passive"))
      (node (ref "J19") (pin "CLK") (pinfunction "1_CLK") (pintype "passive"))
    )
    (net (code "92") (name "Net-(J27-1)") (class "Default")
      (node (ref "J27") (pin "SIG") (pinfunction "1_SIG") (pintype "passive"))
      (node (ref "J28") (pin "CLK") (pinfunction "1_CLK") (pintype "passive"))
    )
    (net (code "93") (name "Net-(Q1-D)") (class "Default")
      (node (ref "D1") (pin "A") (pinfunction "A_A") (pintype "passive"))
      (node (ref "Q1") (pin "3") (pinfunction "D_3") (pintype "bidirectional"))
      (node (ref "U43") (pin "7") (pinfunction "COIL-_7") (pintype "bidirectional"))
    )
    (net (code "94") (name "Net-(Q1-S)") (class "Default")
      (node (ref "Q1") (pin "2") (pinfunction "S_2") (pintype "bidirectional"))
      (node (ref "Q5") (pin "3") (pinfunction "D_3") (pintype "bidirectional"))
    )
    (net (code "95") (name "Net-(Q2-D)") (class "Default")
      (node (ref "D2") (pin "A") (pinfunction "A_A") (pintype "passive"))
      (node (ref "Q2") (pin "3") (pinfunction "D_3") (pintype "bidirectional"))
      (node (ref "U44") (pin "7") (pinfunction "COIL-_7") (pintype "bidirectional"))
    )
    (net (code "96") (name "Net-(Q2-S)") (class "Default")
      (node (ref "Q2") (pin "2") (pinfunction "S_2") (pintype "bidirectional"))
      (node (ref "Q6") (pin "3") (pinfunction "D_3") (pintype "bidirectional"))
    )
    (net (code "97") (name "Net-(Q3-D)") (class "Default")
      (node (ref "D3") (pin "A") (pinfunction "A_A") (pintype "passive"))
      (node (ref "Q3") (pin "3") (pinfunction "D_3") (pintype "bidirectional"))
      (node (ref "U45") (pin "7") (pinfunction "COIL-_7") (pintype "bidirectional"))
    )
    (net (code "98") (name "Net-(Q3-S)") (class "Default")
      (node (ref "Q3") (pin "2") (pinfunction "S_2") (pintype "bidirectional"))
      (node (ref "Q7") (pin "3") (pinfunction "D_3") (pintype "bidirectional"))
    )
    (net (code "99") (name "Net-(Q4-D)") (class "Default")
      (node (ref "D4") (pin "A") (pinfunction "A_A") (pintype "passive"))
      (node (ref "Q4") (pin "3") (pinfunction "D_3") (pintype "bidirectional"))
      (node (ref "U46") (pin "7") (pinfunction "COIL-_7") (pintype "bidirectional"))
    )
    (net (code "100") (name "Net-(Q4-S)") (class "Default")
      (node (ref "Q4") (pin "2") (pinfunction "S_2") (pintype "bidirectional"))
      (node (ref "Q8") (pin "3") (pinfunction "D_3") (pintype "bidirectional"))
    )
    (net (code "101") (name "Net-(Q9-PadS)") (class "Default")
      (node (ref "Q9") (pin "S") (pinfunction "S_S") (pintype "bidirectional"))
      (node (ref "U49") (pin "VIN") (pinfunction "VIN_VIN") (pintype "power_in"))
    )
    (net (code "102") (name "Net-(S1-2)") (class "Default")
      (node (ref "R3") (pin "1") (pinfunction "1_1") (pintype "passive"))
      (node (ref "S1") (pin "1") (pinfunction "2_1") (pintype "passive"))
    )
    (net (code "103") (name "Net-(S2-2)") (class "Default")
      (node (ref "R4") (pin "2") (pinfunction "2_2") (pintype "passive"))
      (node (ref "S2") (pin "1") (pinfunction "2_1") (pintype "passive"))
    )
    (net (code "104") (name "Net-(S3-2)") (class "Default")
      (node (ref "R5") (pin "2") (pinfunction "2_2") (pintype "passive"))
      (node (ref "S3") (pin "1") (pinfunction "2_1") (pintype "passive"))
    )
    (net (code "105") (name "Net-(S4-2)") (class "Default")
      (node (ref "R6") (pin "2") (pinfunction "2_2") (pintype "passive"))
      (node (ref "S4") (pin "1") (pinfunction "2_1") (pintype "passive"))
    )
    (net (code "106") (name "Net-(U1-DIN)") (class "Default")
      (node (ref "R1") (pin "2") (pinfunction "2_2") (pintype "passive"))
      (node (ref "U1") (pin "1") (pinfunction "DIN_1") (pintype "input"))
    )
    (net (code "107") (name "Net-(U1-DOUT)") (class "Default")
      (node (ref "U1") (pin "3") (pinfunction "DOUT_3") (pintype "output"))
      (node (ref "U2") (pin "1") (pinfunction "DIN_1") (pintype "input"))
    )
    (net (code "108") (name "Net-(U2-DOUT)") (class "Default")
      (node (ref "U2") (pin "3") (pinfunction "DOUT_3") (pintype "output"))
      (node (ref "U3") (pin "1") (pinfunction "DIN_1") (pintype "input"))
    )
    (net (code "109") (name "Net-(U3-DOUT)") (class "Default")
      (node (ref "U3") (pin "3") (pinfunction "DOUT_3") (pintype "output"))
      (node (ref "U4") (pin "1") (pinfunction "DIN_1") (pintype "input"))
    )
    (net (code "110") (name "Net-(U4-DOUT)") (class "Default")
      (node (ref "U4") (pin "3") (pinfunction "DOUT_3") (pintype "output"))
      (node (ref "U5") (pin "1") (pinfunction "DIN_1") (pintype "input"))
    )
    (net (code "111") (name "Net-(U5-DOUT)") (class "Default")
      (node (ref "U5") (pin "3") (pinfunction "DOUT_3") (pintype "output"))
      (node (ref "U6") (pin "1") (pinfunction "DIN_1") (pintype "input"))
    )
    (net (code "112") (name "Net-(U6-DOUT)") (class "Default")
      (node (ref "U6") (pin "3") (pinfunction "DOUT_3") (pintype "output"))
      (node (ref "U7") (pin "1") (pinfunction "DIN_1") (pintype "input"))
    )
    (net (code "113") (name "Net-(U7-DOUT)") (class "Default")
      (node (ref "U7") (pin "3") (pinfunction "DOUT_3") (pintype "output"))
      (node (ref "U8") (pin "1") (pinfunction "DIN_1") (pintype "input"))
    )
    (net (code "114") (name "Net-(U8-DOUT)") (class "Default")
      (node (ref "U8") (pin "3") (pinfunction "DOUT_3") (pintype "output"))
      (node (ref "U9") (pin "1") (pinfunction "DIN_1") (pintype "input"))
    )
    (net (code "115") (name "Net-(U10-B)") (class "Default")
      (node (ref "R1") (pin "1") (pinfunction "1_1") (pintype "passive"))
      (node (ref "U10") (pin "4") (pinfunction "B_4") (pintype "bidirectional"))
    )
    (net (code "116") (name "Net-(U10-OE)") (class "Default")
      (node (ref "R2") (pin "2") (pinfunction "2_2") (pintype "passive"))
      (node (ref "U10") (pin "5") (pinfunction "OE_5") (pintype "bidirectional"))
    )
    (net (code "117") (name "Net-(U11-DIN)") (class "Default")
      (node (ref "U11") (pin "1") (pinfunction "DIN_1") (pintype "input"))
      (node (ref "U9") (pin "3") (pinfunction "DOUT_3") (pintype "output"))
    )
    (net (code "118") (name "Net-(U11-DOUT)") (class "Default")
      (node (ref "U11") (pin "3") (pinfunction "DOUT_3") (pintype "output"))
      (node (ref "U12") (pin "1") (pinfunction "DIN_1") (pintype "input"))
    )
    (net (code "119") (name "Net-(U12-DOUT)") (class "Default")
      (node (ref "U12") (pin "3") (pinfunction "DOUT_3") (pintype "output"))
      (node (ref "U13") (pin "1") (pinfunction "DIN_1") (pintype "input"))
    )
    (net (code "120") (name "Net-(U13-DOUT)") (class "Default")
      (node (ref "U13") (pin "3") (pinfunction "DOUT_3") (pintype "output"))
      (node (ref "U14") (pin "1") (pinfunction "DIN_1") (pintype "input"))
    )
    (net (code "121") (name "Net-(U14-DOUT)") (class "Default")
      (node (ref "U14") (pin "3") (pinfunction "DOUT_3") (pintype "output"))
      (node (ref "U15") (pin "1") (pinfunction "DIN_1") (pintype "input"))
    )
    (net (code "122") (name "Net-(U15-DOUT)") (class "Default")
      (node (ref "U15") (pin "3") (pinfunction "DOUT_3") (pintype "output"))
      (node (ref "U16") (pin "1") (pinfunction "DIN_1") (pintype "input"))
    )
    (net (code "123") (name "Net-(U16-DOUT)") (class "Default")
      (node (ref "U16") (pin "3") (pinfunction "DOUT_3") (pintype "output"))
      (node (ref "U17") (pin "1") (pinfunction "DIN_1") (pintype "input"))
    )
    (net (code "124") (name "Net-(U17-DOUT)") (class "Default")
      (node (ref "U17") (pin "3") (pinfunction "DOUT_3") (pintype "output"))
      (node (ref "U18") (pin "1") (pinfunction "DIN_1") (pintype "input"))
    )
    (net (code "125") (name "Net-(U18-DOUT)") (class "Default")
      (node (ref "U18") (pin "3") (pinfunction "DOUT_3") (pintype "output"))
      (node (ref "U19") (pin "1") (pinfunction "DIN_1") (pintype "input"))
    )
    (net (code "126") (name "Net-(U19-DOUT)") (class "Default")
      (node (ref "U19") (pin "3") (pinfunction "DOUT_3") (pintype "output"))
      (node (ref "U20") (pin "1") (pinfunction "DIN_1") (pintype "input"))
    )
    (net (code "127") (name "Net-(U20-DOUT)") (class "Default")
      (node (ref "U20") (pin "3") (pinfunction "DOUT_3") (pintype "output"))
      (node (ref "U21") (pin "1") (pinfunction "DIN_1") (pintype "input"))
    )
    (net (code "128") (name "Net-(U21-DOUT)") (class "Default")
      (node (ref "U21") (pin "3") (pinfunction "DOUT_3") (pintype "output"))
      (node (ref "U22") (pin "1") (pinfunction "DIN_1") (pintype "input"))
    )
    (net (code "129") (name "Net-(U22-DOUT)") (class "Default")
      (node (ref "U22") (pin "3") (pinfunction "DOUT_3") (pintype "output"))
      (node (ref "U23") (pin "1") (pinfunction "DIN_1") (pintype "input"))
    )
    (net (code "130") (name "Net-(U23-DOUT)") (class "Default")
      (node (ref "U23") (pin "3") (pinfunction "DOUT_3") (pintype "output"))
      (node (ref "U24") (pin "1") (pinfunction "DIN_1") (pintype "input"))
    )
    (net (code "131") (name "Net-(U24-DOUT)") (class "Default")
      (node (ref "U24") (pin "3") (pinfunction "DOUT_3") (pintype "output"))
      (node (ref "U25") (pin "1") (pinfunction "DIN_1") (pintype "input"))
    )
    (net (code "132") (name "Net-(U25-DOUT)") (class "Default")
      (node (ref "U25") (pin "3") (pinfunction "DOUT_3") (pintype "output"))
      (node (ref "U26") (pin "1") (pinfunction "DIN_1") (pintype "input"))
    )
    (net (code "133") (name "Net-(U26-DOUT)") (class "Default")
      (node (ref "U26") (pin "3") (pinfunction "DOUT_3") (pintype "output"))
      (node (ref "U27") (pin "1") (pinfunction "DIN_1") (pintype "input"))
    )
    (net (code "134") (name "Net-(U27-DOUT)") (class "Default")
      (node (ref "U27") (pin "3") (pinfunction "DOUT_3") (pintype "output"))
      (node (ref "U28") (pin "1") (pinfunction "DIN_1") (pintype "input"))
    )
    (net (code "135") (name "Net-(U28-DOUT)") (class "Default")
      (node (ref "U28") (pin "3") (pinfunction "DOUT_3") (pintype "output"))
      (node (ref "U29") (pin "1") (pinfunction "DIN_1") (pintype "input"))
    )
    (net (code "136") (name "Net-(U29-DOUT)") (class "Default")
      (node (ref "U29") (pin "3") (pinfunction "DOUT_3") (pintype "output"))
      (node (ref "U30") (pin "1") (pinfunction "DIN_1") (pintype "input"))
    )
    (net (code "137") (name "Net-(U30-DOUT)") (class "Default")
      (node (ref "U30") (pin "3") (pinfunction "DOUT_3") (pintype "output"))
      (node (ref "U31") (pin "1") (pinfunction "DIN_1") (pintype "input"))
    )
    (net (code "138") (name "Net-(U31-DOUT)") (class "Default")
      (node (ref "U31") (pin "3") (pinfunction "DOUT_3") (pintype "output"))
      (node (ref "U32") (pin "1") (pinfunction "DIN_1") (pintype "input"))
    )
    (net (code "139") (name "Net-(U32-DOUT)") (class "Default")
      (node (ref "U32") (pin "3") (pinfunction "DOUT_3") (pintype "output"))
      (node (ref "U33") (pin "1") (pinfunction "DIN_1") (pintype "input"))
    )
    (net (code "140") (name "Net-(U33-DOUT)") (class "Default")
      (node (ref "U33") (pin "3") (pinfunction "DOUT_3") (pintype "output"))
      (node (ref "U34") (pin "1") (pinfunction "DIN_1") (pintype "input"))
    )
    (net (code "141") (name "Net-(U34-DOUT)") (class "Default")
      (node (ref "U34") (pin "3") (pinfunction "DOUT_3") (pintype "output"))
      (node (ref "U35") (pin "1") (pinfunction "DIN_1") (pintype "input"))
    )
    (net (code "142") (name "Net-(U35-DOUT)") (class "Default")
      (node (ref "U35") (pin "3") (pinfunction "DOUT_3") (pintype "output"))
      (node (ref "U36") (pin "1") (pinfunction "DIN_1") (pintype "input"))
    )
    (net (code "143") (name "Net-(U36-DOUT)") (class "Default")
      (node (ref "U36") (pin "3") (pinfunction "DOUT_3") (pintype "output"))
      (node (ref "U37") (pin "1") (pinfunction "DIN_1") (pintype "input"))
    )
    (net (code "144") (name "Net-(U37-DOUT)") (class "Default")
      (node (ref "U37") (pin "3") (pinfunction "DOUT_3") (pintype "output"))
      (node (ref "U38") (pin "1") (pinfunction "DIN_1") (pintype "input"))
    )
    (net (code "145") (name "Net-(U38-DOUT)") (class "Default")
      (node (ref "U38") (pin "3") (pinfunction "DOUT_3") (pintype "output"))
      (node (ref "U39") (pin "1") (pinfunction "DIN_1") (pintype "input"))
    )
    (net (code "146") (name "Net-(U39-DOUT)") (class "Default")
      (node (ref "U39") (pin "3") (pinfunction "DOUT_3") (pintype "output"))
      (node (ref "U40") (pin "1") (pinfunction "DIN_1") (pintype "input"))
    )
    (net (code "147") (name "Net-(U40-DOUT)") (class "Default")
      (node (ref "U40") (pin "3") (pinfunction "DOUT_3") (pintype "output"))
      (node (ref "U41") (pin "1") (pinfunction "DIN_1") (pintype "input"))
    )
    (net (code "148") (name "Net-(U41-DOUT)") (class "Default")
      (node (ref "U41") (pin "3") (pinfunction "DOUT_3") (pintype "output"))
      (node (ref "U42") (pin "1") (pinfunction "DIN_1") (pintype "input"))
    )
    (net (code "149") (name "Net-(U43-NC_A)") (class "Default")
      (node (ref "C32") (pin "2") (pinfunction "2_2") (pintype "passive"))
      (node (ref "U43") (pin "6") (pinfunction "NC_A_6") (pintype "bidirectional"))
    )
    (net (code "150") (name "Net-(U44-NC_A)") (class "Default")
      (node (ref "C33") (pin "2") (pinfunction "2_2") (pintype "passive"))
      (node (ref "U44") (pin "6") (pinfunction "NC_A_6") (pintype "bidirectional"))
    )
    (net (code "151") (name "Net-(U45-NC_A)") (class "Default")
      (node (ref "C34") (pin "2") (pinfunction "2_2") (pintype "passive"))
      (node (ref "U45") (pin "6") (pinfunction "NC_A_6") (pintype "bidirectional"))
    )
    (net (code "152") (name "Net-(U46-NC_A)") (class "Default")
      (node (ref "C35") (pin "2") (pinfunction "2_2") (pintype "passive"))
      (node (ref "U46") (pin "6") (pinfunction "NC_A_6") (pintype "bidirectional"))
    )
    (net (code "153") (name "Net-(U47-FB1)") (class "Default")
      (node (ref "R19") (pin "1") (pinfunction "1_1") (pintype "passive"))
      (node (ref "U47") (pin "E4") (pinfunction "FB1_E4") (pintype "input"))
    )
    (net (code "154") (name "Net-(U47-FB2)") (class "Default")
      (node (ref "R21") (pin "1") (pinfunction "1_1") (pintype "passive"))
      (node (ref "U47") (pin "A4") (pinfunction "FB2_A4") (pintype "input"))
    )
    (net (code "155") (name "Net-(U47-FREQ)") (class "Default")
      (node (ref "R20") (pin "1") (pinfunction "1_1") (pintype "passive"))
      (node (ref "U47") (pin "C4") (pinfunction "FREQ_C4") (pintype "input"))
    )
    (net (code "156") (name "Net-(U47-TRACK{slash}SS1)") (class "Default")
      (node (ref "C39") (pin "2") (pinfunction "2_2") (pintype "passive"))
      (node (ref "U47") (pin "E3") (pinfunction "TRACK/SS1_E3") (pintype "input"))
    )
    (net (code "157") (name "Net-(U47-TRACK{slash}SS2)") (class "Default")
      (node (ref "C38") (pin "2") (pinfunction "2_2") (pintype "passive"))
      (node (ref "U47") (pin "A3") (pinfunction "TRACK/SS2_A3") (pintype "input"))
    )
    (net (code "158") (name "Net-(U48-B1)") (class "Default")
      (node (ref "J29") (pin "4") (pinfunction "4_4") (pintype "passive"))
      (node (ref "U48") (pin "6") (pinfunction "B1_6") (pintype "bidirectional"))
    )
    (net (code "159") (name "Net-(U48-BGND)") (class "Default")
      (node (ref "C41") (pin "2") (pinfunction "2_2") (pintype "passive"))
      (node (ref "J29") (pin "5") (pinfunction "5_5") (pintype "passive"))
      (node (ref "U48") (pin "5") (pinfunction "BGND_5") (pintype "bidirectional"))
    )
    (net (code "160") (name "Net-(U48-BVDD)") (class "Default")
      (node (ref "C41") (pin "1") (pinfunction "1_1") (pintype "passive"))
      (node (ref "J29") (pin "1") (pinfunction "1_1") (pintype "passive"))
      (node (ref "U48") (pin "8") (pinfunction "BVDD_8") (pintype "bidirectional"))
    )
    (net (code "161") (name "RELAY_AND_0") (class "Default")
      (node (ref "Q5") (pin "1") (pinfunction "G_1") (pintype "bidirectional"))
      (node (ref "R11") (pin "2") (pinfunction "2_2") (pintype "passive"))
      (node (ref "U50") (pin "8") (pinfunction "P04_8") (pintype "bidirectional"))
    )
    (net (code "162") (name "RELAY_AND_1") (class "Default")
      (node (ref "Q6") (pin "1") (pinfunction "G_1") (pintype "bidirectional"))
      (node (ref "R13") (pin "2") (pinfunction "2_2") (pintype "passive"))
      (node (ref "U50") (pin "6") (pinfunction "P02_6") (pintype "bidirectional"))
    )
    (net (code "163") (name "RELAY_AND_2") (class "Default")
      (node (ref "Q7") (pin "1") (pinfunction "G_1") (pintype "bidirectional"))
      (node (ref "R15") (pin "2") (pinfunction "2_2") (pintype "passive"))
      (node (ref "U50") (pin "4") (pinfunction "P00_4") (pintype "bidirectional"))
    )
    (net (code "164") (name "RELAY_AND_3") (class "Default")
      (node (ref "Q8") (pin "1") (pinfunction "G_1") (pintype "bidirectional"))
      (node (ref "R17") (pin "2") (pinfunction "2_2") (pintype "passive"))
      (node (ref "U50") (pin "20") (pinfunction "P17_20") (pintype "bidirectional"))
    )
    (net (code "165") (name "RELAY_MECH_0") (class "Default")
      (node (ref "C28") (pin "2") (pinfunction "2_2") (pintype "passive"))
      (node (ref "Q1") (pin "1") (pinfunction "G_1") (pintype "bidirectional"))
      (node (ref "R12") (pin "2") (pinfunction "2_2") (pintype "passive"))
      (node (ref "R3") (pin "2") (pinfunction "2_2") (pintype "passive"))
      (node (ref "U50") (pin "9") (pinfunction "P05_9") (pintype "bidirectional"))
    )
    (net (code "166") (name "RELAY_MECH_1") (class "Default")
      (node (ref "C29") (pin "2") (pinfunction "2_2") (pintype "passive"))
      (node (ref "Q2") (pin "1") (pinfunction "G_1") (pintype "bidirectional"))
      (node (ref "R14") (pin "2") (pinfunction "2_2") (pintype "passive"))
      (node (ref "R4") (pin "1") (pinfunction "1_1") (pintype "passive"))
      (node (ref "U50") (pin "7") (pinfunction "P03_7") (pintype "bidirectional"))
    )
    (net (code "167") (name "RELAY_MECH_2") (class "Default")
      (node (ref "C30") (pin "2") (pinfunction "2_2") (pintype "passive"))
      (node (ref "Q3") (pin "1") (pinfunction "G_1") (pintype "bidirectional"))
      (node (ref "R16") (pin "2") (pinfunction "2_2") (pintype "passive"))
      (node (ref "R5") (pin "1") (pinfunction "1_1") (pintype "passive"))
      (node (ref "U50") (pin "5") (pinfunction "P01_5") (pintype "bidirectional"))
    )
    (net (code "168") (name "RELAY_MECH_3") (class "Default")
      (node (ref "C31") (pin "2") (pinfunction "2_2") (pintype "passive"))
      (node (ref "Q4") (pin "1") (pinfunction "G_1") (pintype "bidirectional"))
      (node (ref "R18") (pin "2") (pinfunction "2_2") (pintype "passive"))
      (node (ref "R6") (pin "1") (pinfunction "1_1") (pintype "passive"))
      (node (ref "U50") (pin "19") (pinfunction "P16_19") (pintype "bidirectional"))
    )
    (net (code "169") (name "unconnected-(U42-DOUT-Pad3)") (class "Default")
      (node (ref "U42") (pin "3") (pinfunction "DOUT_3") (pintype "output"))
    )
    (net (code "170") (name "unconnected-(U43-COM_B-Pad3)") (class "Default")
      (node (ref "U43") (pin "3") (pinfunction "COM_B_3") (pintype "bidirectional"))
    )
    (net (code "171") (name "unconnected-(U43-NC_B-Pad2)") (class "Default")
      (node (ref "U43") (pin "2") (pinfunction "NC_B_2") (pintype "bidirectional"))
    )
    (net (code "172") (name "unconnected-(U43-NO_B-Pad4)") (class "Default")
      (node (ref "U43") (pin "4") (pinfunction "NO_B_4") (pintype "bidirectional"))
    )
    (net (code "173") (name "unconnected-(U44-COM_B-Pad3)") (class "Default")
      (node (ref "U44") (pin "3") (pinfunction "COM_B_3") (pintype "bidirectional"))
    )
    (net (code "174") (name "unconnected-(U44-NC_B-Pad2)") (class "Default")
      (node (ref "U44") (pin "2") (pinfunction "NC_B_2") (pintype "bidirectional"))
    )
    (net (code "175") (name "unconnected-(U44-NO_B-Pad4)") (class "Default")
      (node (ref "U44") (pin "4") (pinfunction "NO_B_4") (pintype "bidirectional"))
    )
    (net (code "176") (name "unconnected-(U45-COM_B-Pad3)") (class "Default")
      (node (ref "U45") (pin "3") (pinfunction "COM_B_3") (pintype "bidirectional"))
    )
    (net (code "177") (name "unconnected-(U45-NC_B-Pad2)") (class "Default")
      (node (ref "U45") (pin "2") (pinfunction "NC_B_2") (pintype "bidirectional"))
    )
    (net (code "178") (name "unconnected-(U45-NO_B-Pad4)") (class "Default")
      (node (ref "U45") (pin "4") (pinfunction "NO_B_4") (pintype "bidirectional"))
    )
    (net (code "179") (name "unconnected-(U46-COM_B-Pad3)") (class "Default")
      (node (ref "U46") (pin "3") (pinfunction "COM_B_3") (pintype "bidirectional"))
    )
    (net (code "180") (name "unconnected-(U46-NC_B-Pad2)") (class "Default")
      (node (ref "U46") (pin "2") (pinfunction "NC_B_2") (pintype "bidirectional"))
    )
    (net (code "181") (name "unconnected-(U46-NO_B-Pad4)") (class "Default")
      (node (ref "U46") (pin "4") (pinfunction "NO_B_4") (pintype "bidirectional"))
    )
    (net (code "182") (name "unconnected-(U47-COMP1-PadE5)") (class "Default")
      (node (ref "U47") (pin "E5") (pinfunction "COMP1_E5") (pintype "bidirectional"))
    )
    (net (code "183") (name "unconnected-(U47-COMP2-PadA5)") (class "Default")
      (node (ref "U47") (pin "A5") (pinfunction "COMP2_A5") (pintype "bidirectional"))
    )
    (net (code "184") (name "unconnected-(U47-INTVCC-PadC3)") (class "Default")
      (node (ref "U47") (pin "C3") (pinfunction "INTVCC_C3") (pintype "output"))
    )
    (net (code "185") (name "unconnected-(U47-PGOOD1-PadD4)") (class "Default")
      (node (ref "U47") (pin "D4") (pinfunction "PGOOD1_D4") (pintype "open_collector"))
    )
    (net (code "186") (name "unconnected-(U48-AVDD{slash}NC-Pad3)") (class "Default")
      (node (ref "U48") (pin "3") (pinfunction "AVDD/NC_3") (pintype "bidirectional"))
    )
    (net (code "187") (name "unconnected-(U48-BGND{slash}NC-Pad7)") (class "Default")
      (node (ref "U48") (pin "7") (pinfunction "BGND/NC_7") (pintype "bidirectional"))
    )
    (net (code "188") (name "unconnected-(U50-P10-Pad13)") (class "Default")
      (node (ref "U50") (pin "13") (pinfunction "P10_13") (pintype "bidirectional"))
    )
    (net (code "189") (name "unconnected-(U50-P12-Pad15)") (class "Default")
      (node (ref "U50") (pin "15") (pinfunction "P12_15") (pintype "bidirectional"))
    )
    (net (code "190") (name "unconnected-(U51-COUT-Pad11)") (class "Default")
      (node (ref "U51") (pin "11") (pinfunction "COUT_11") (pintype "output"))
    )
    (net (code "191") (name "unconnected-(U51-DOUT-Pad13)") (class "Default")
      (node (ref "U51") (pin "13") (pinfunction "DOUT_13") (pintype "output"))
    )
    (net (code "192") (name "unconnected-(U53-BOUT+-Pad6)") (class "Default")
      (node (ref "U53") (pin "6") (pinfunction "BOUT+_6") (pintype "output"))
    )
    (net (code "193") (name "unconnected-(U53-BOUT--Pad5)") (class "Default")
      (node (ref "U53") (pin "5") (pinfunction "BOUT-_5") (pintype "output"))
    )
  )
)
